# FindMeSAT_MB_1V3.net
KiCad netlist of a schematic drawn in EAGLE
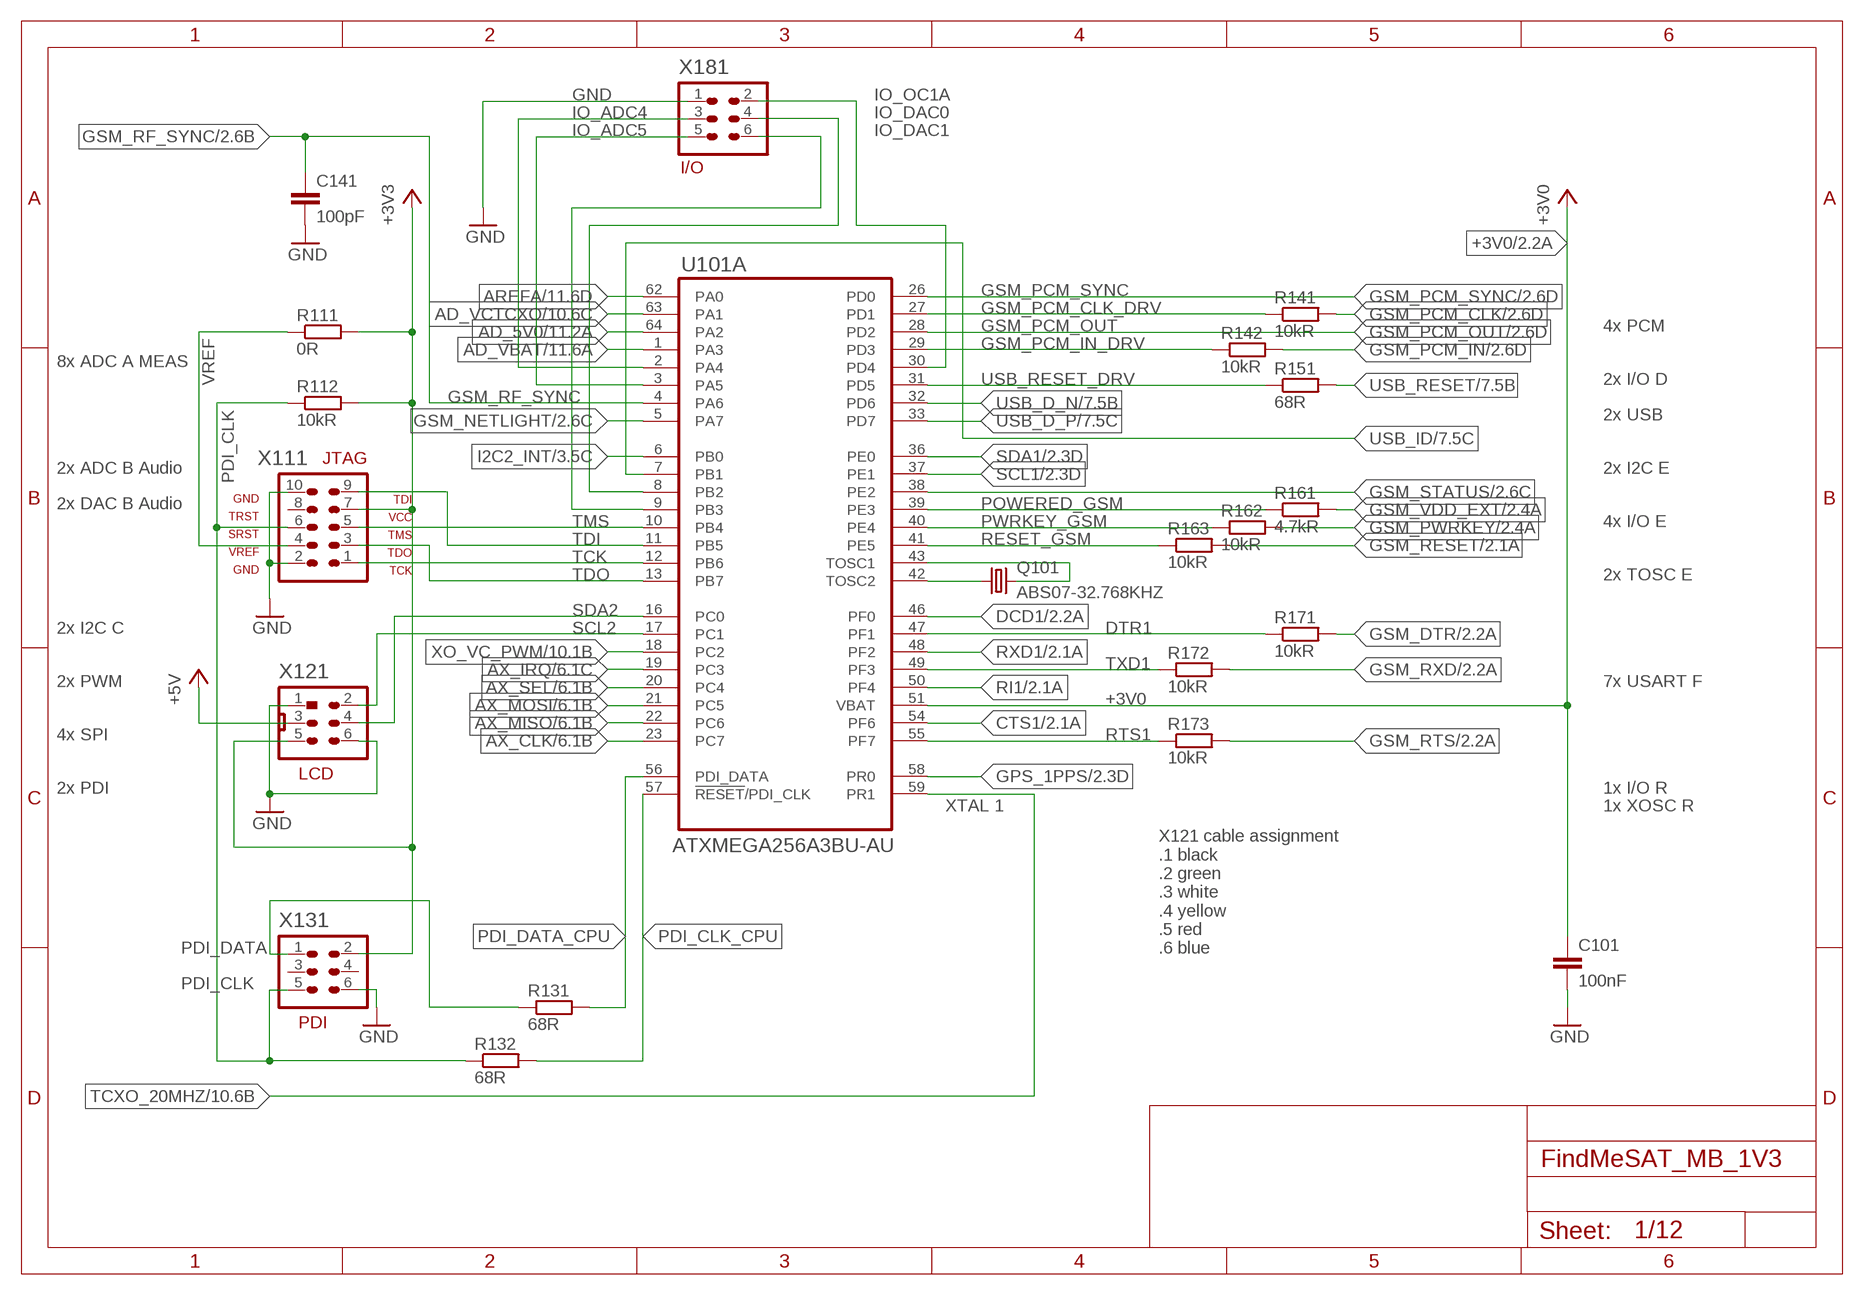
[diagram p0: schematic, sheet 1]
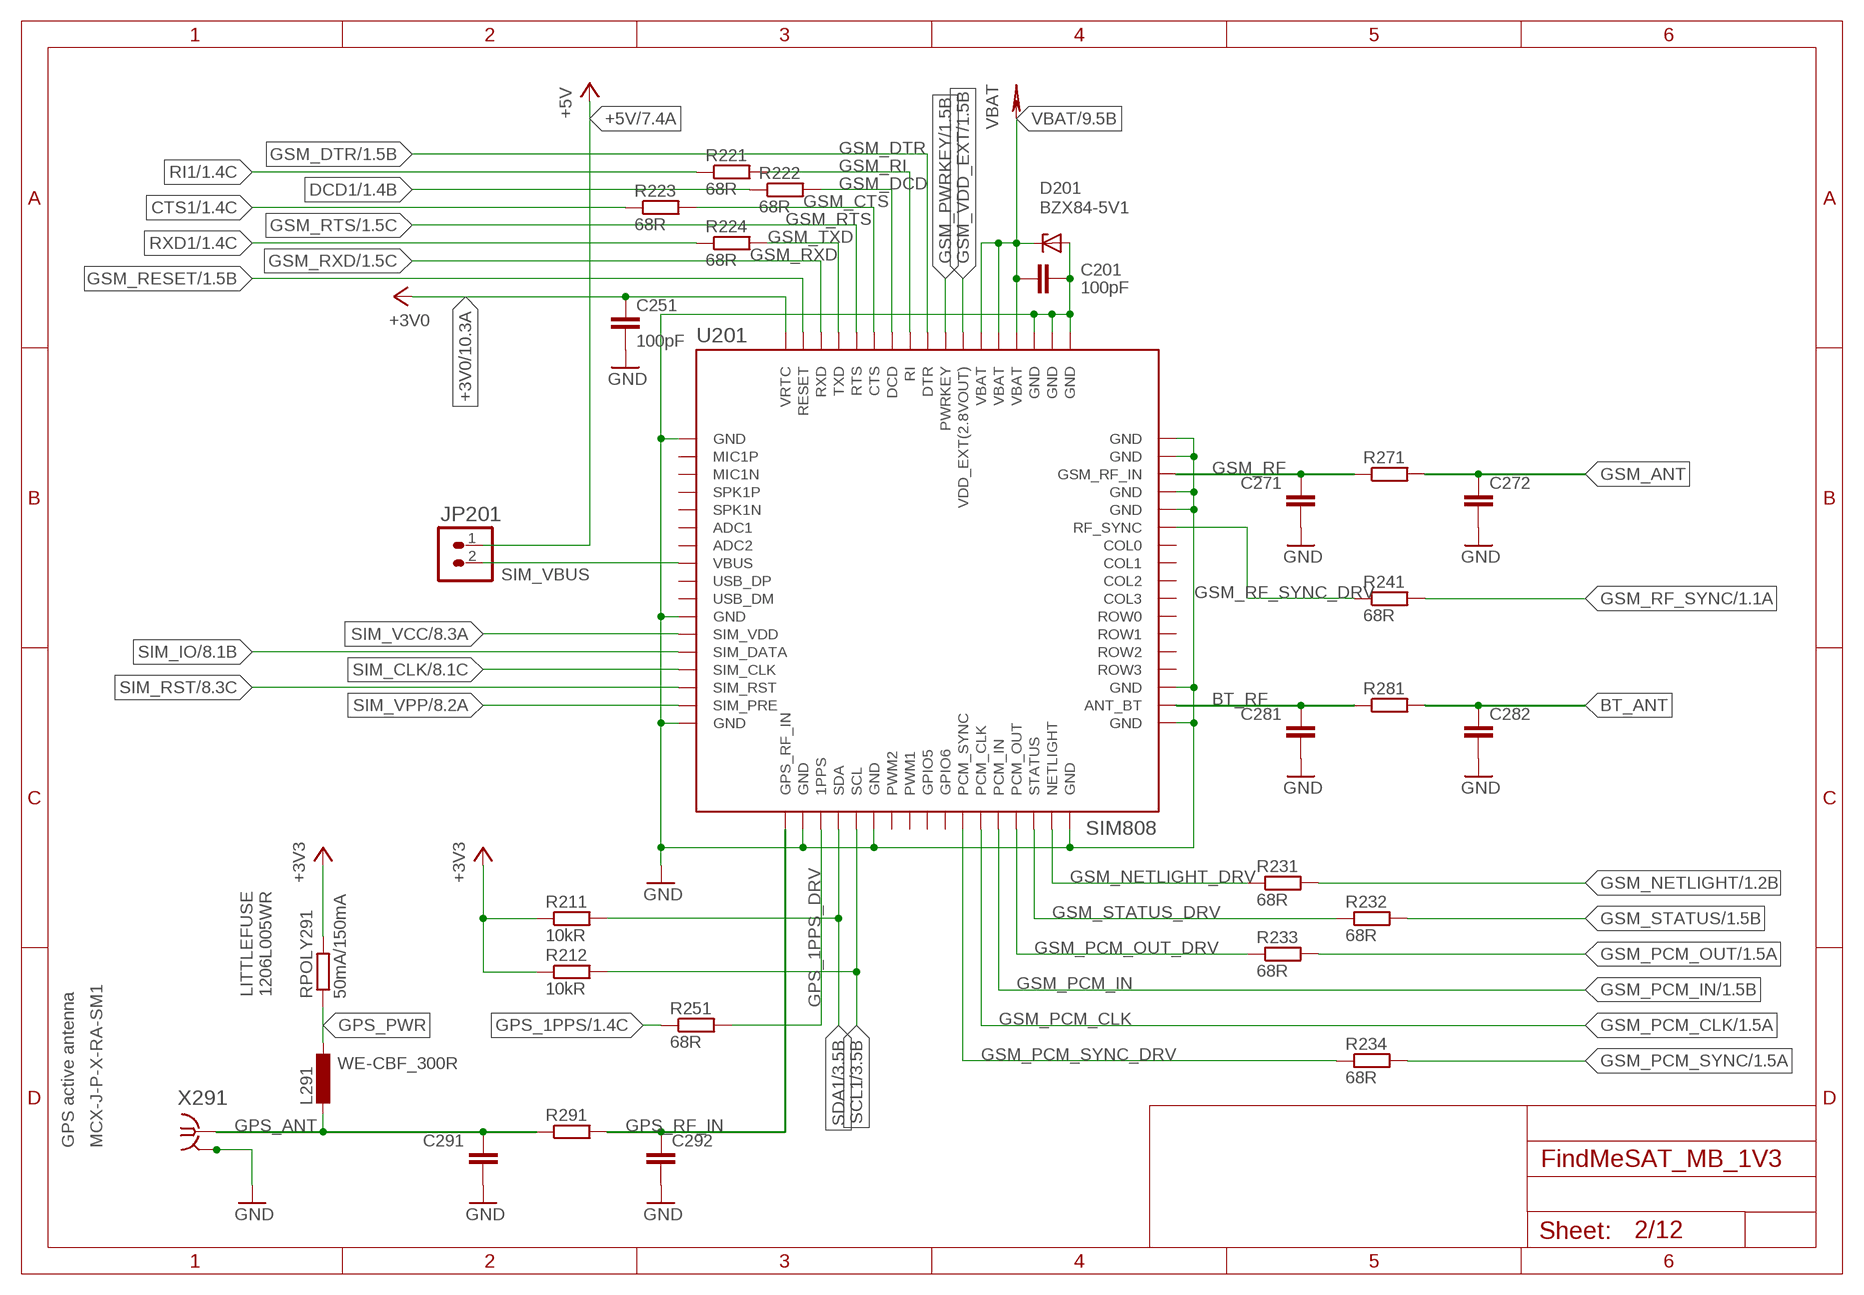
[diagram p1: schematic, sheet 2]
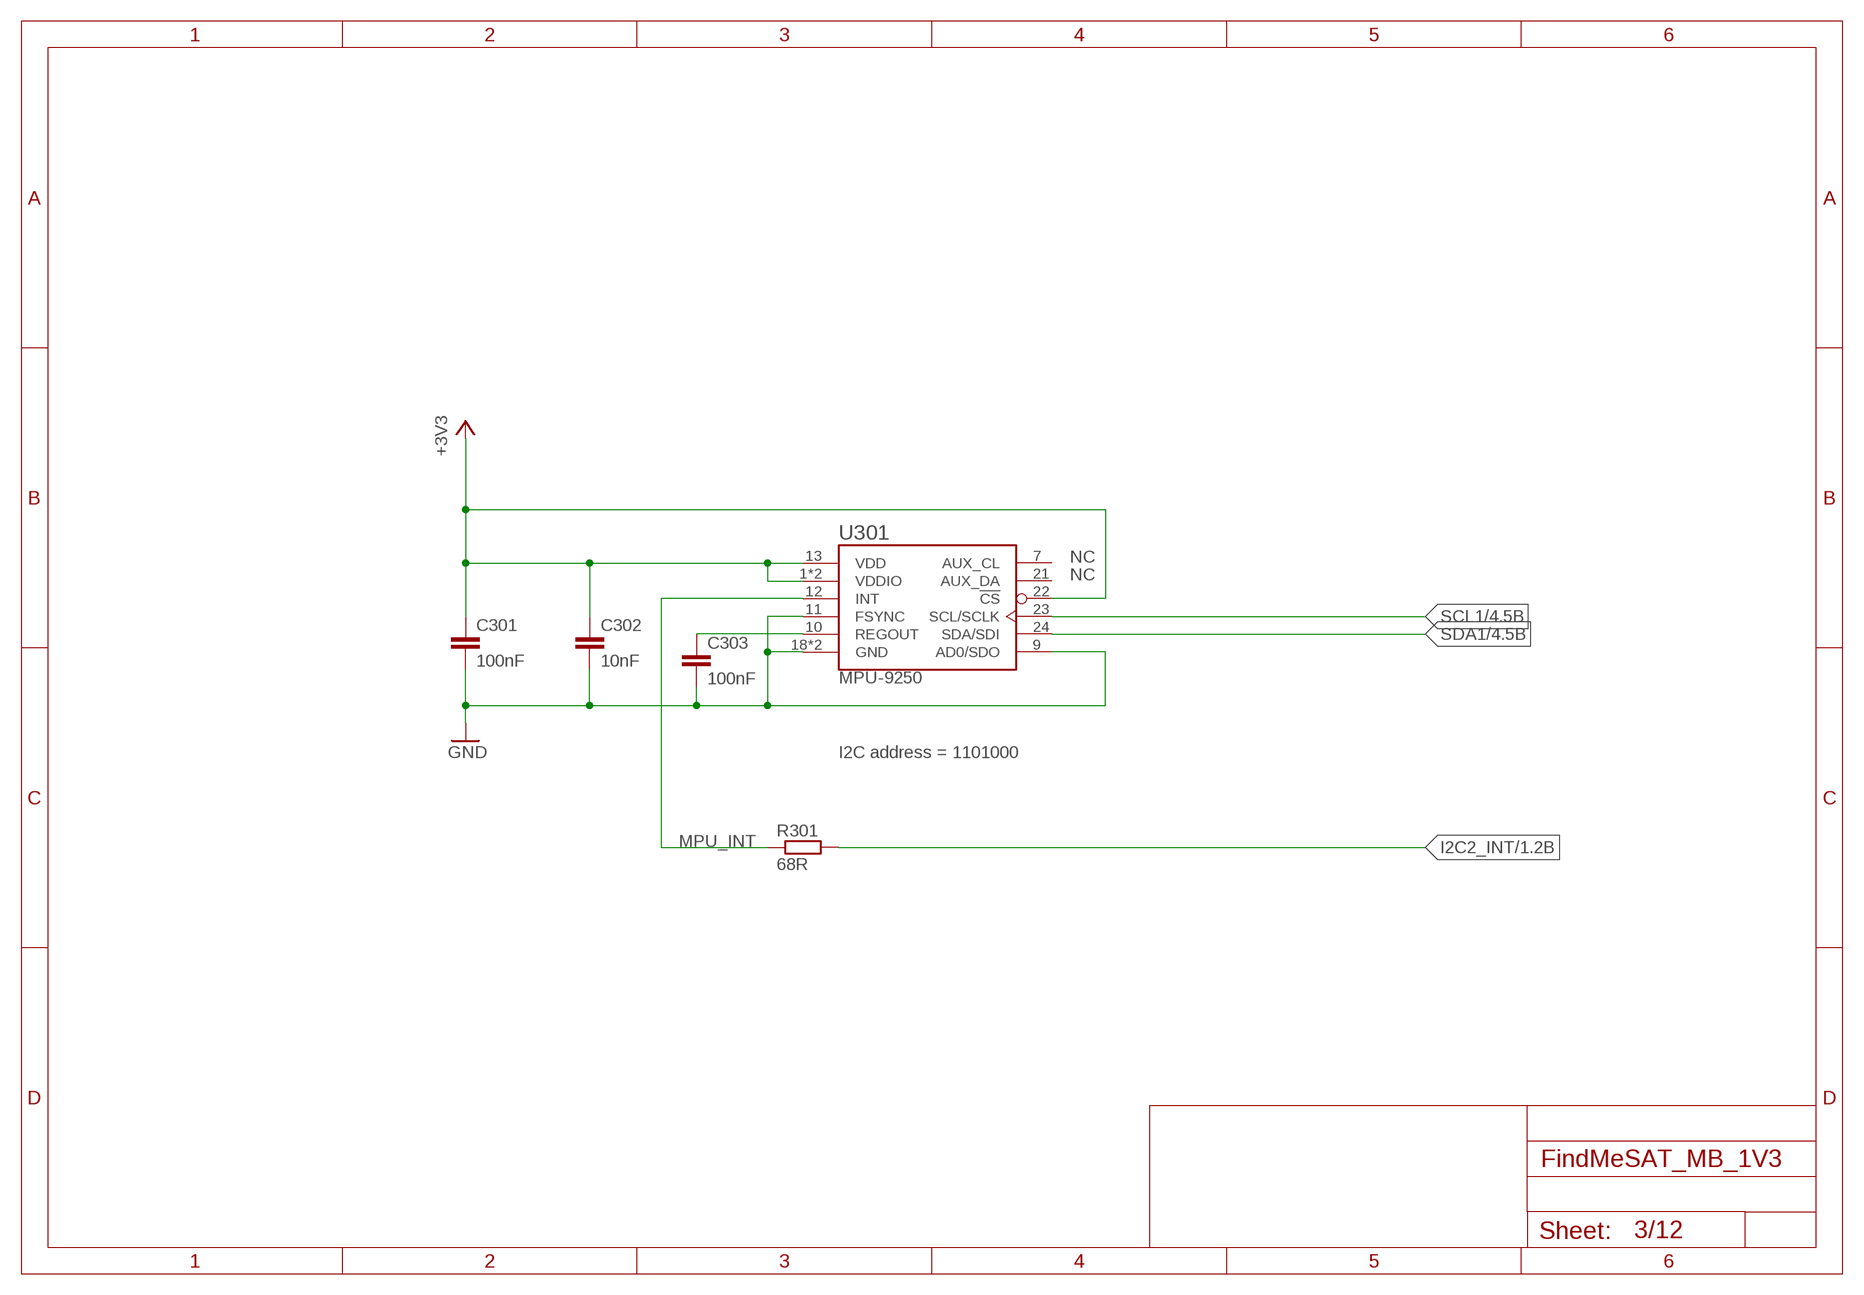
[diagram p2: schematic, sheet 3]
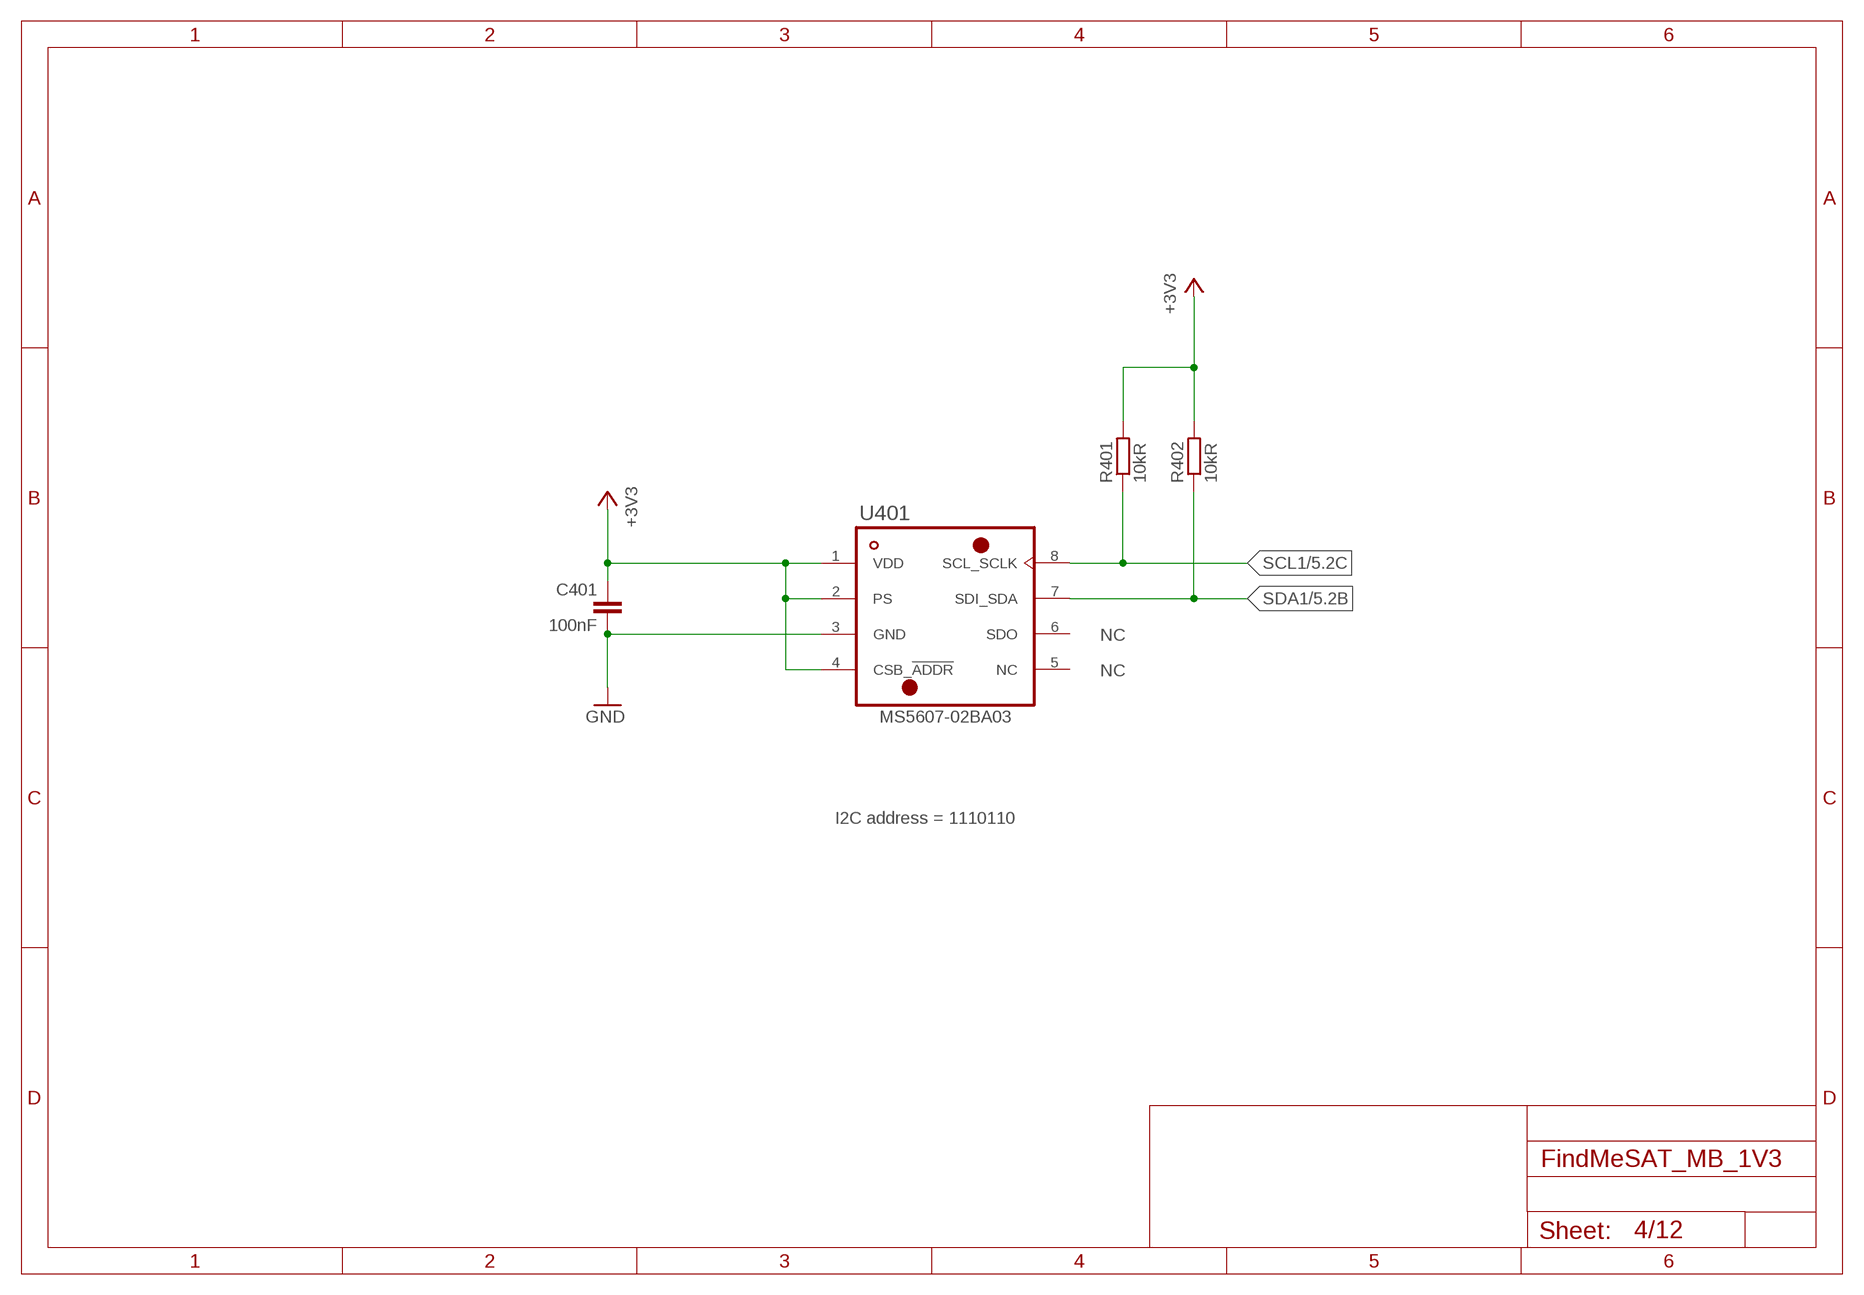
[diagram p3: schematic, sheet 4]
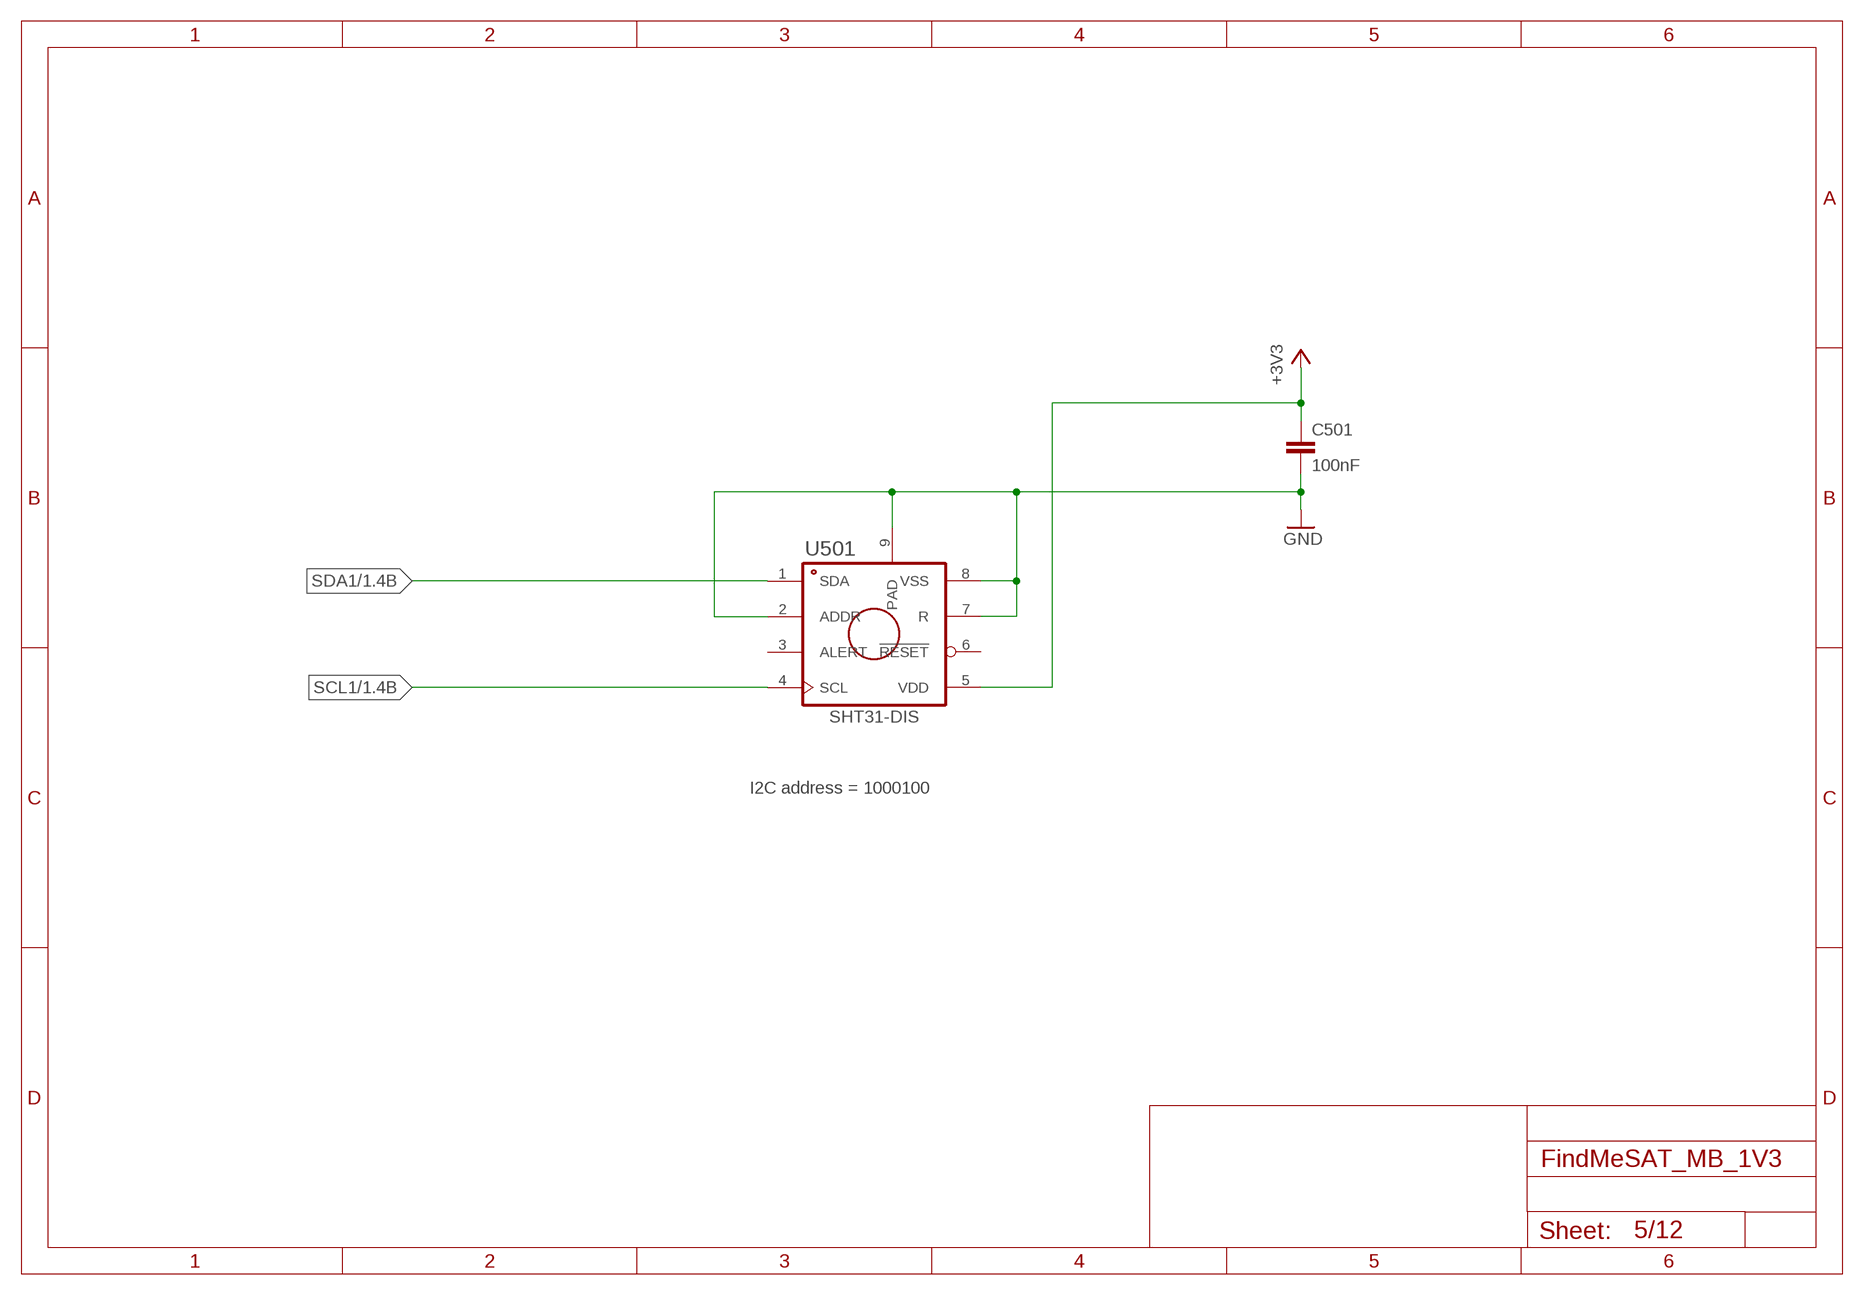
[diagram p4: schematic, sheet 5]
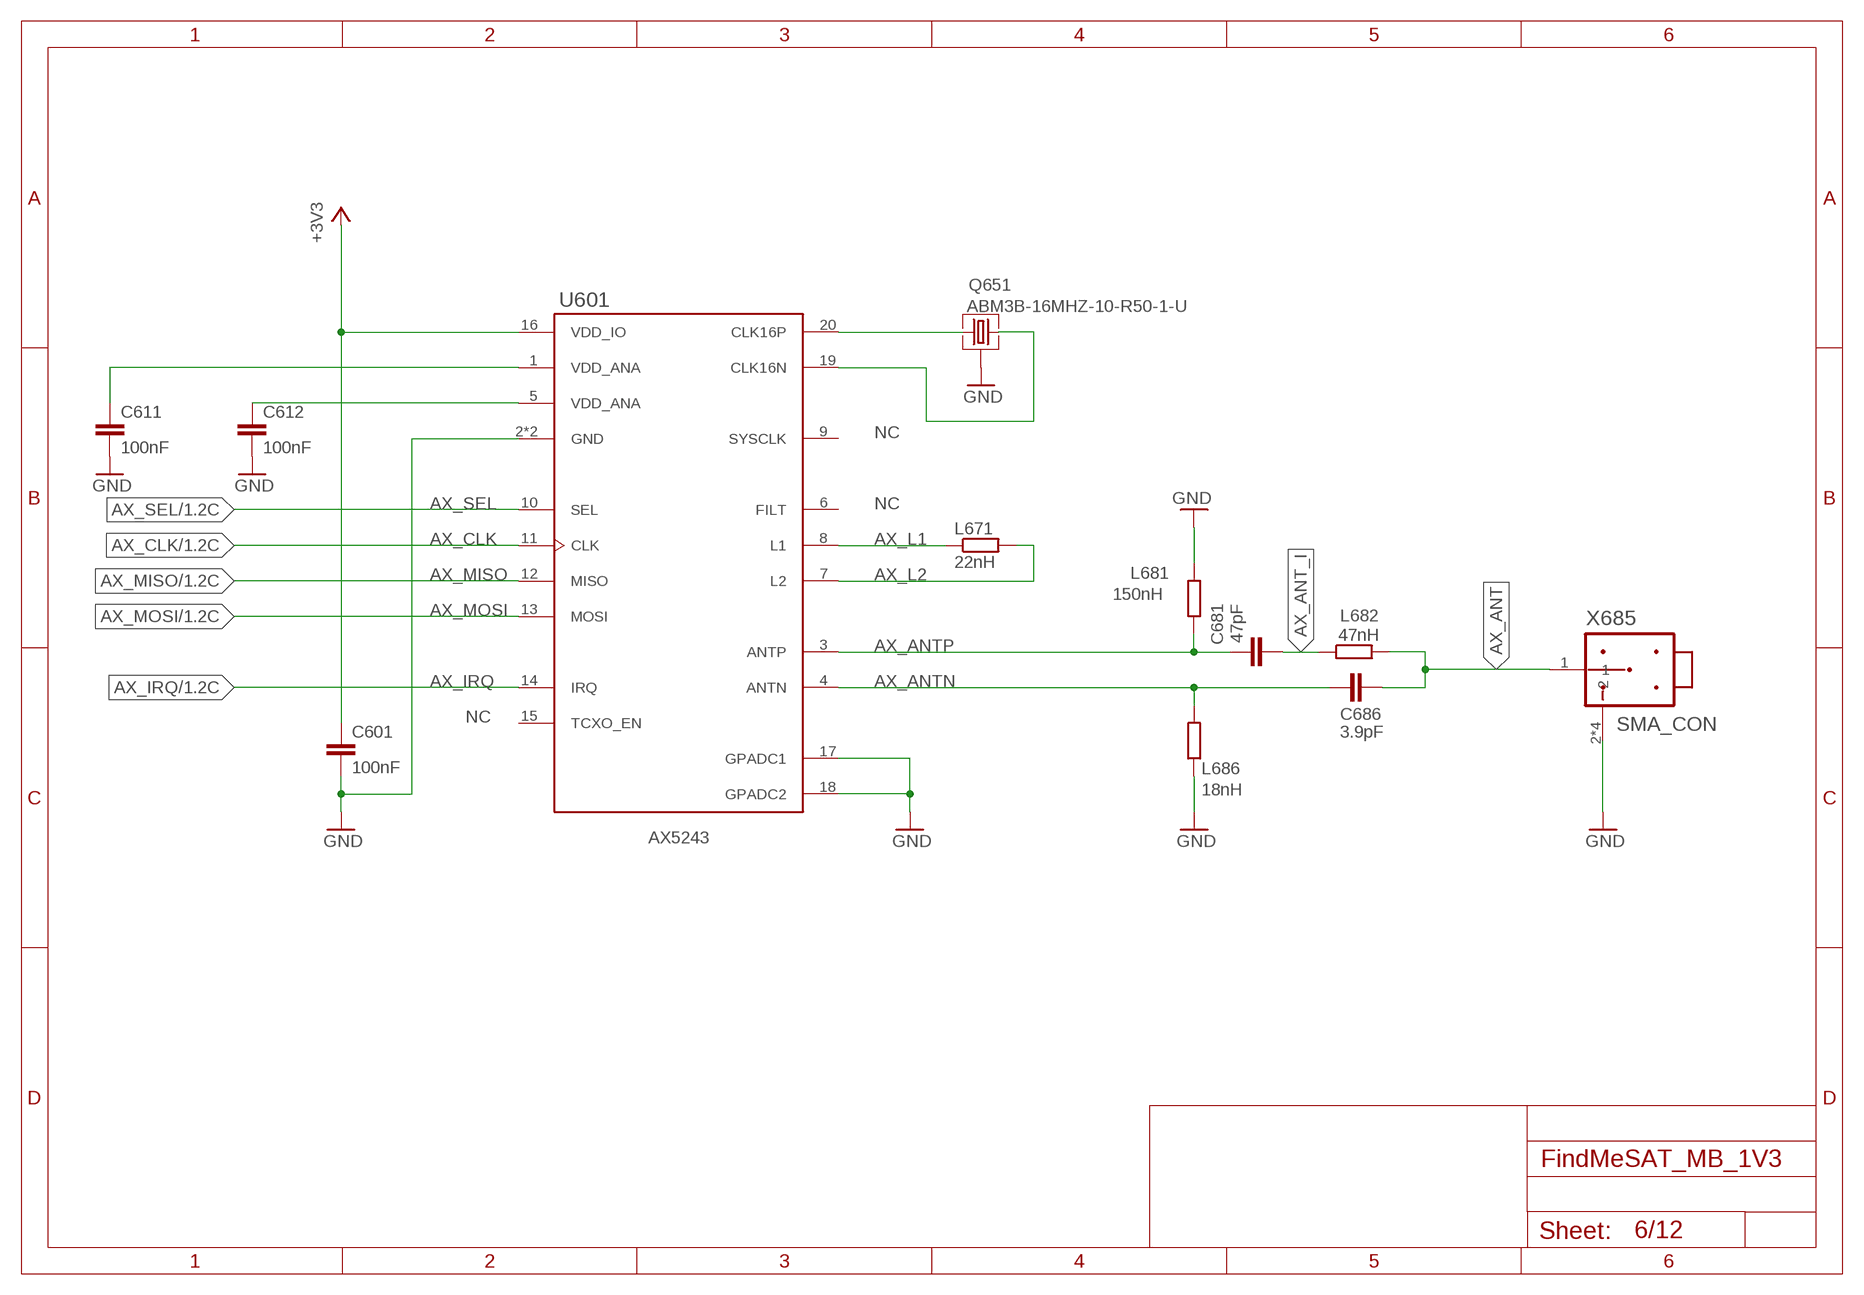
[diagram p5: schematic, sheet 6]
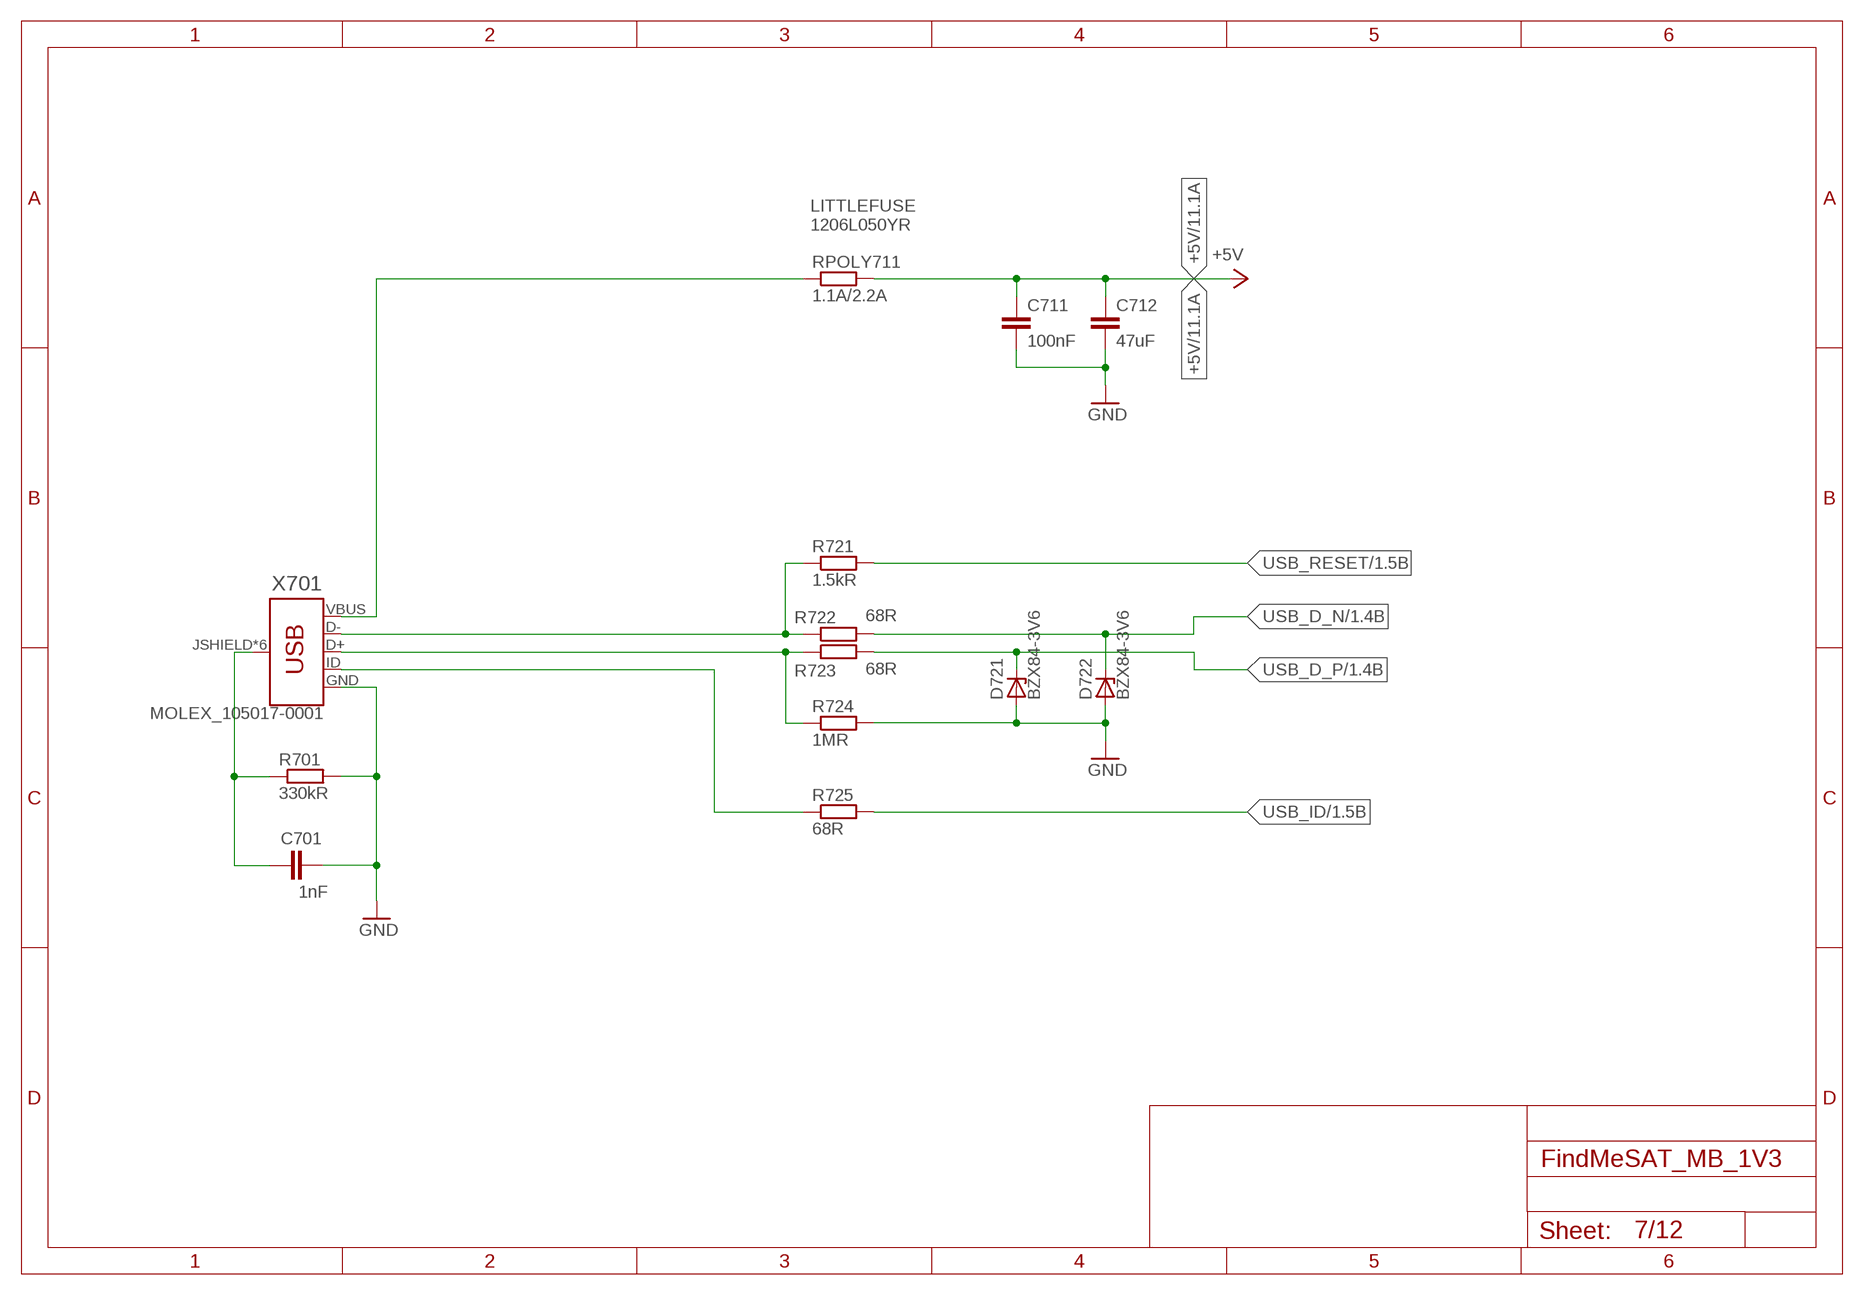
[diagram p6: schematic, sheet 7]
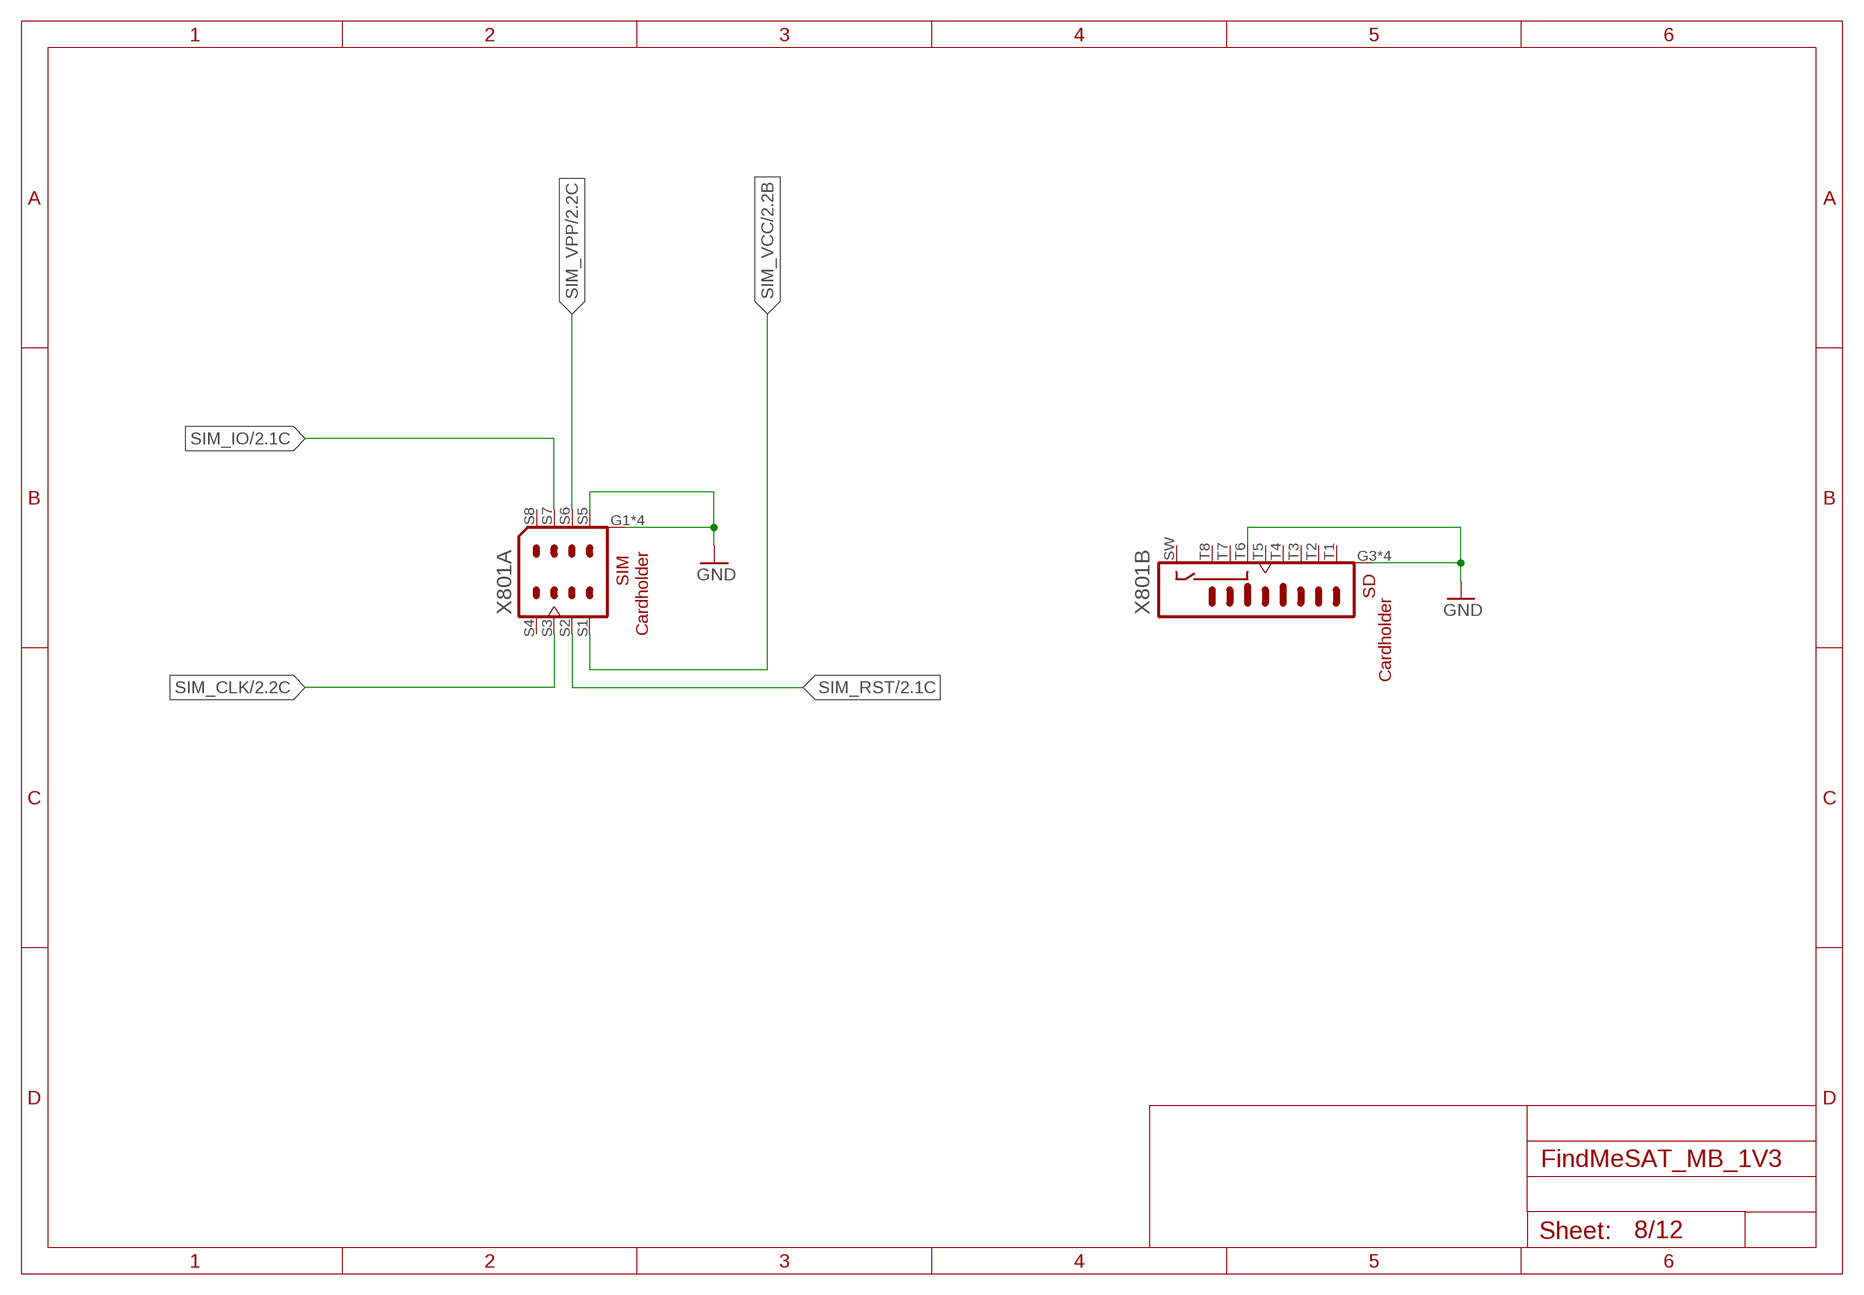
[diagram p7: schematic, sheet 8]
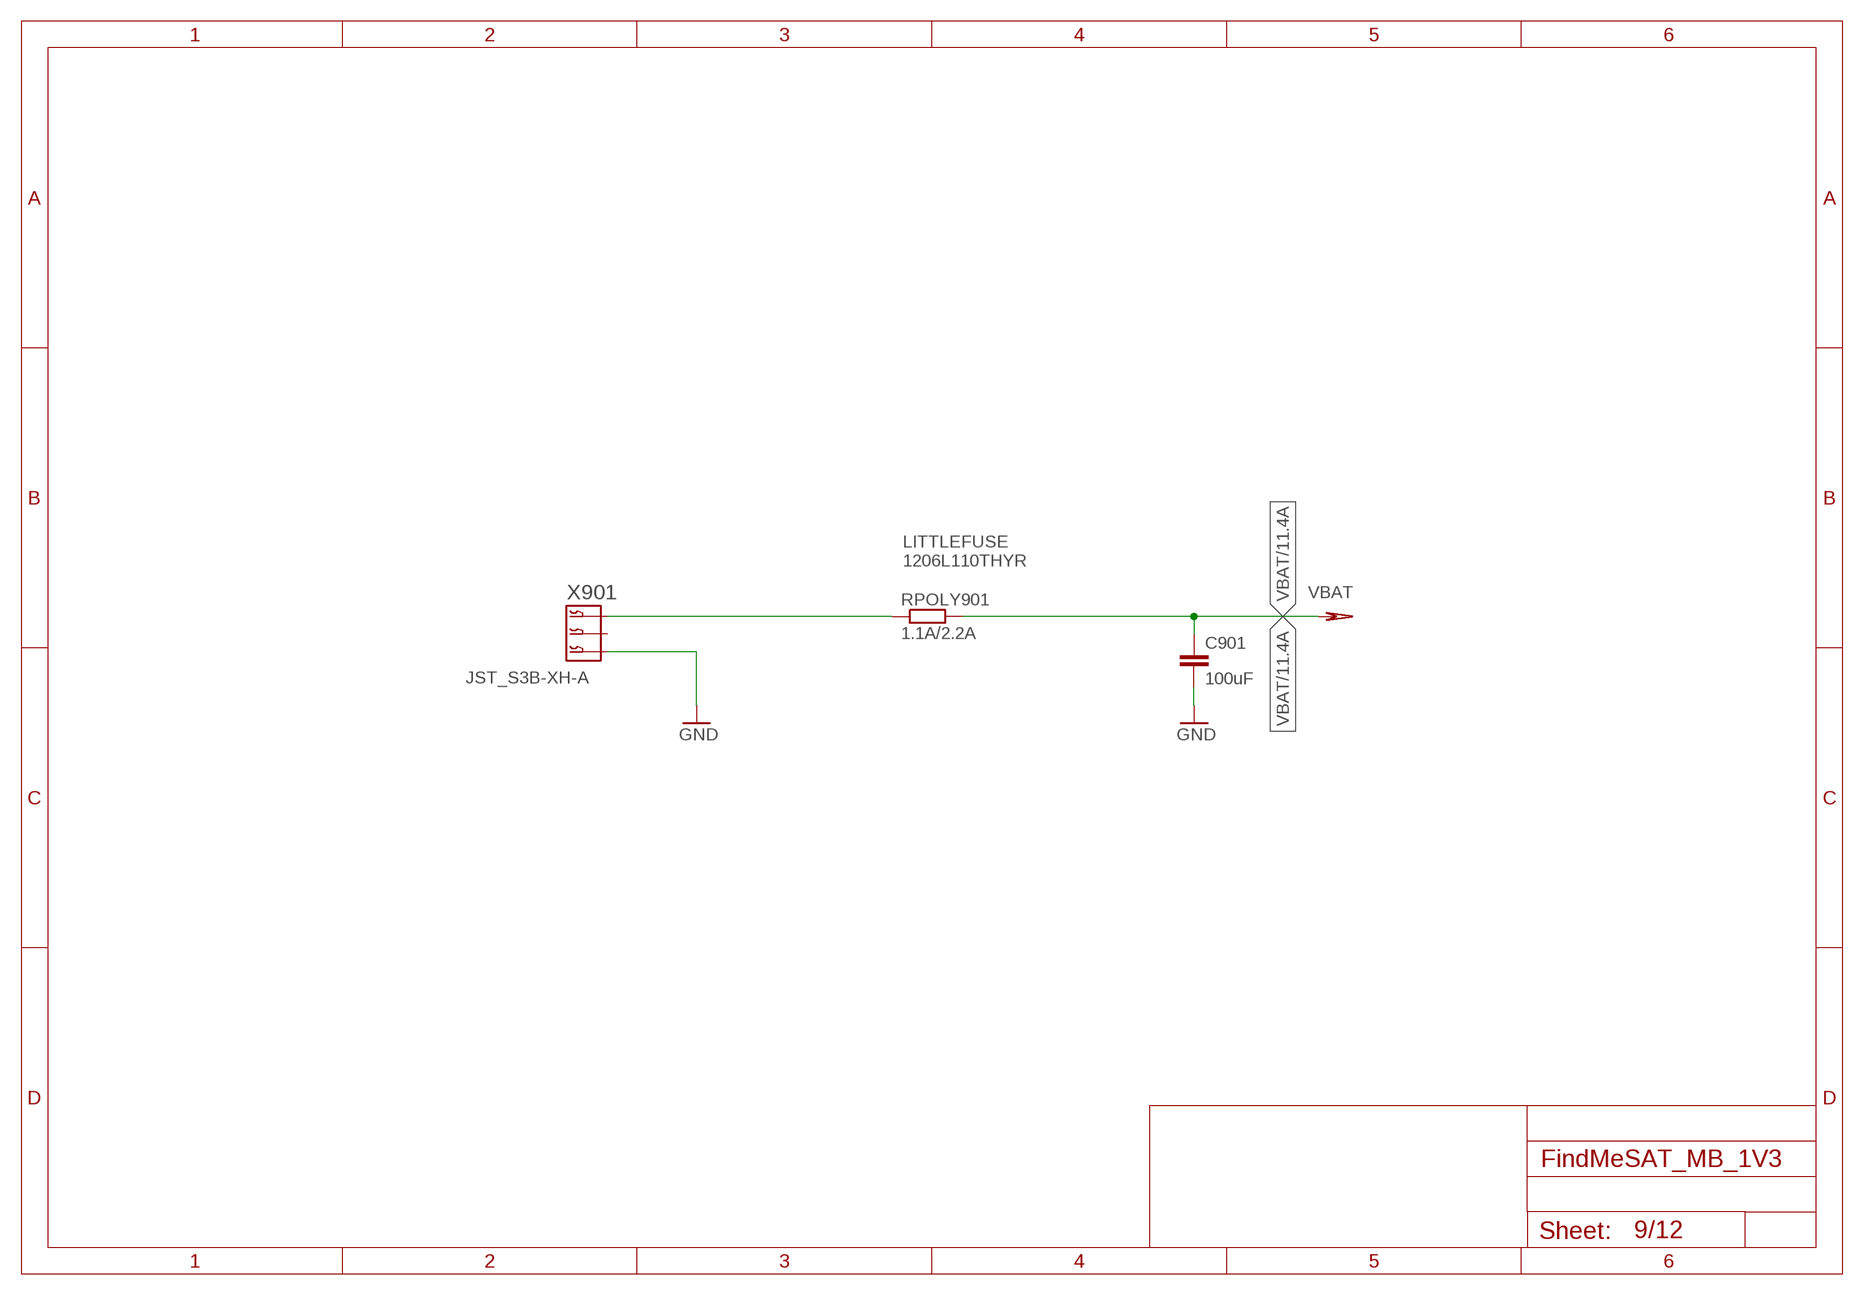
[diagram p8: schematic, sheet 9]
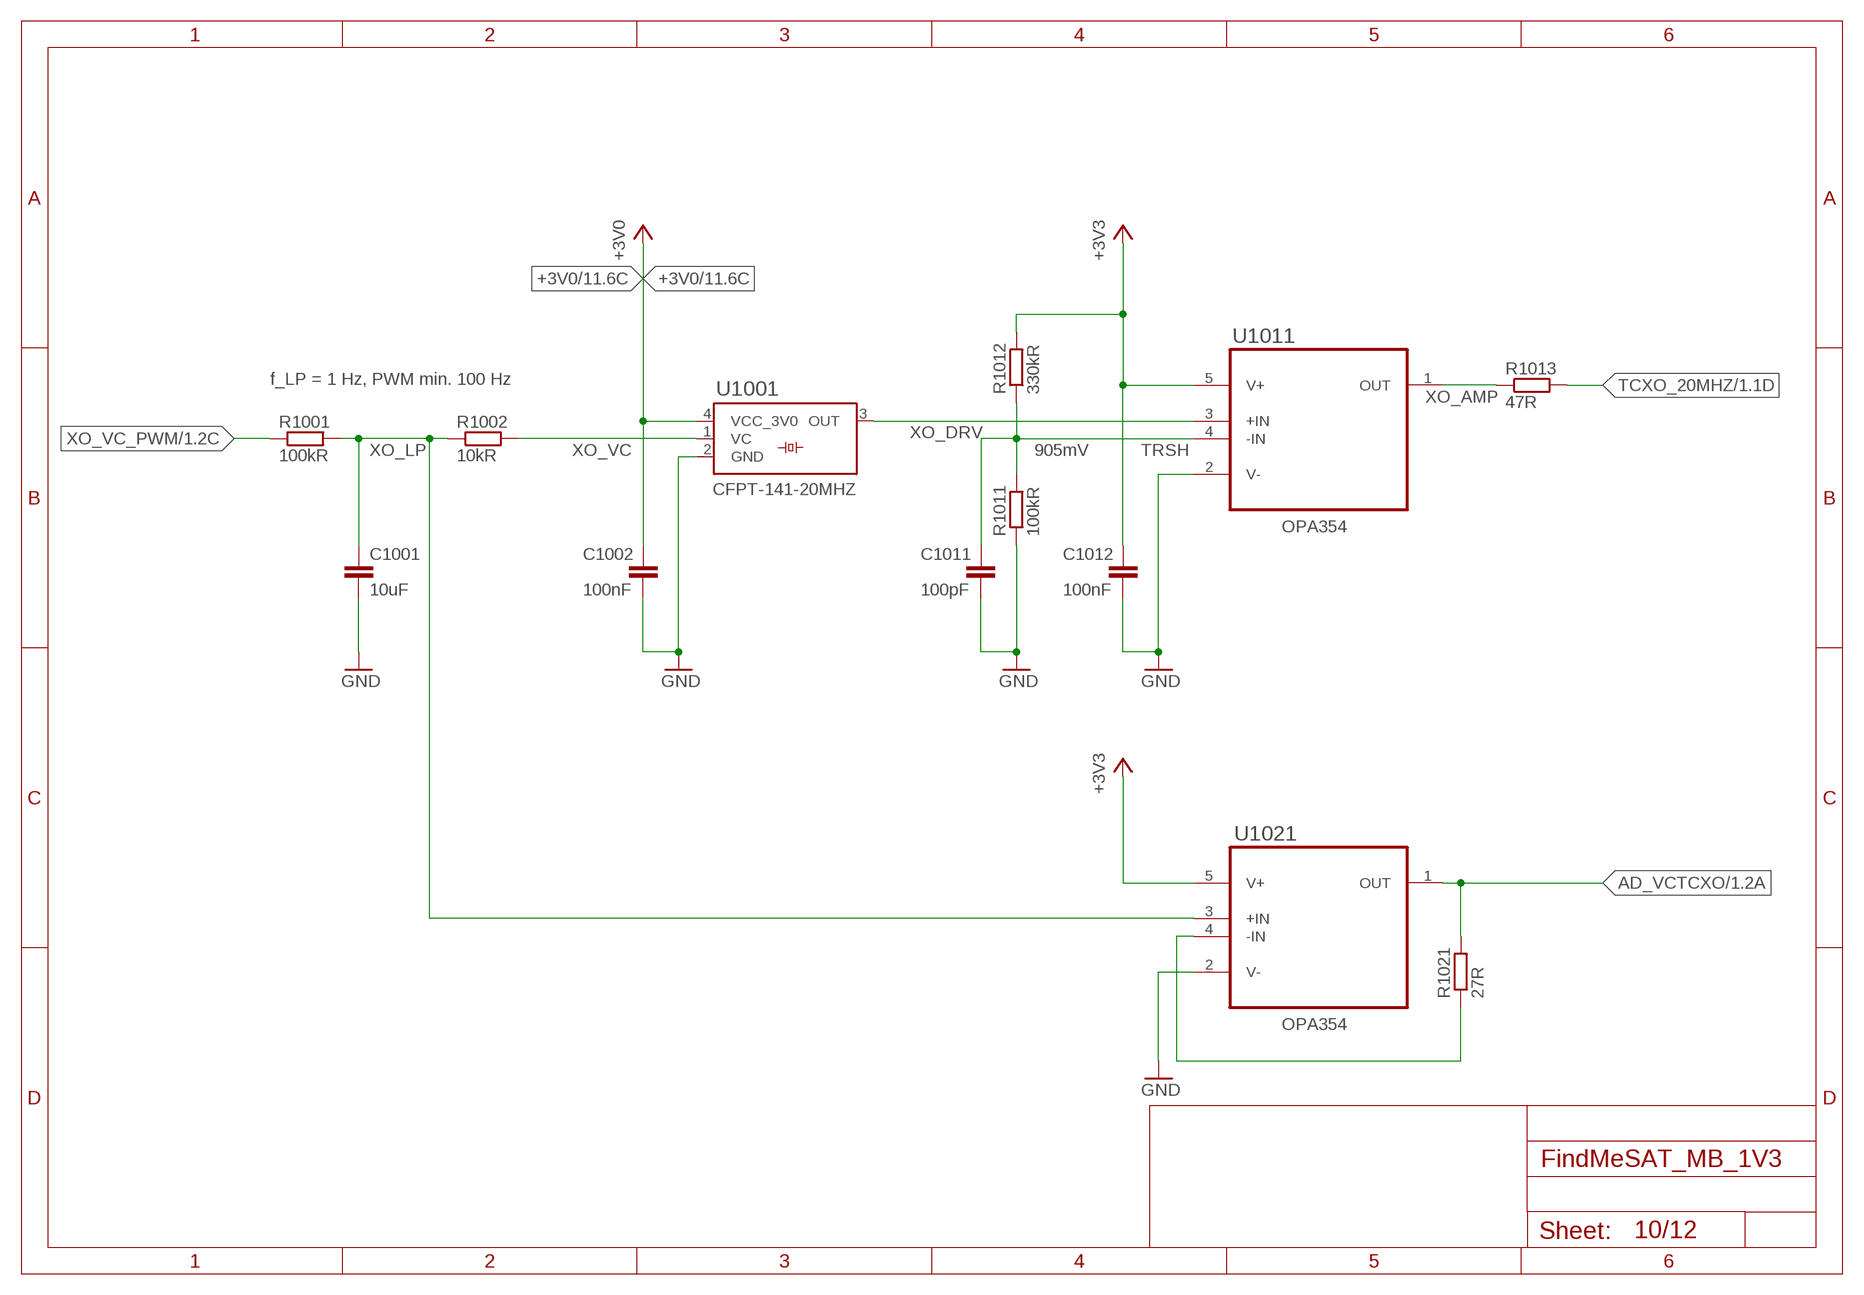
[diagram p9: schematic, sheet 10]
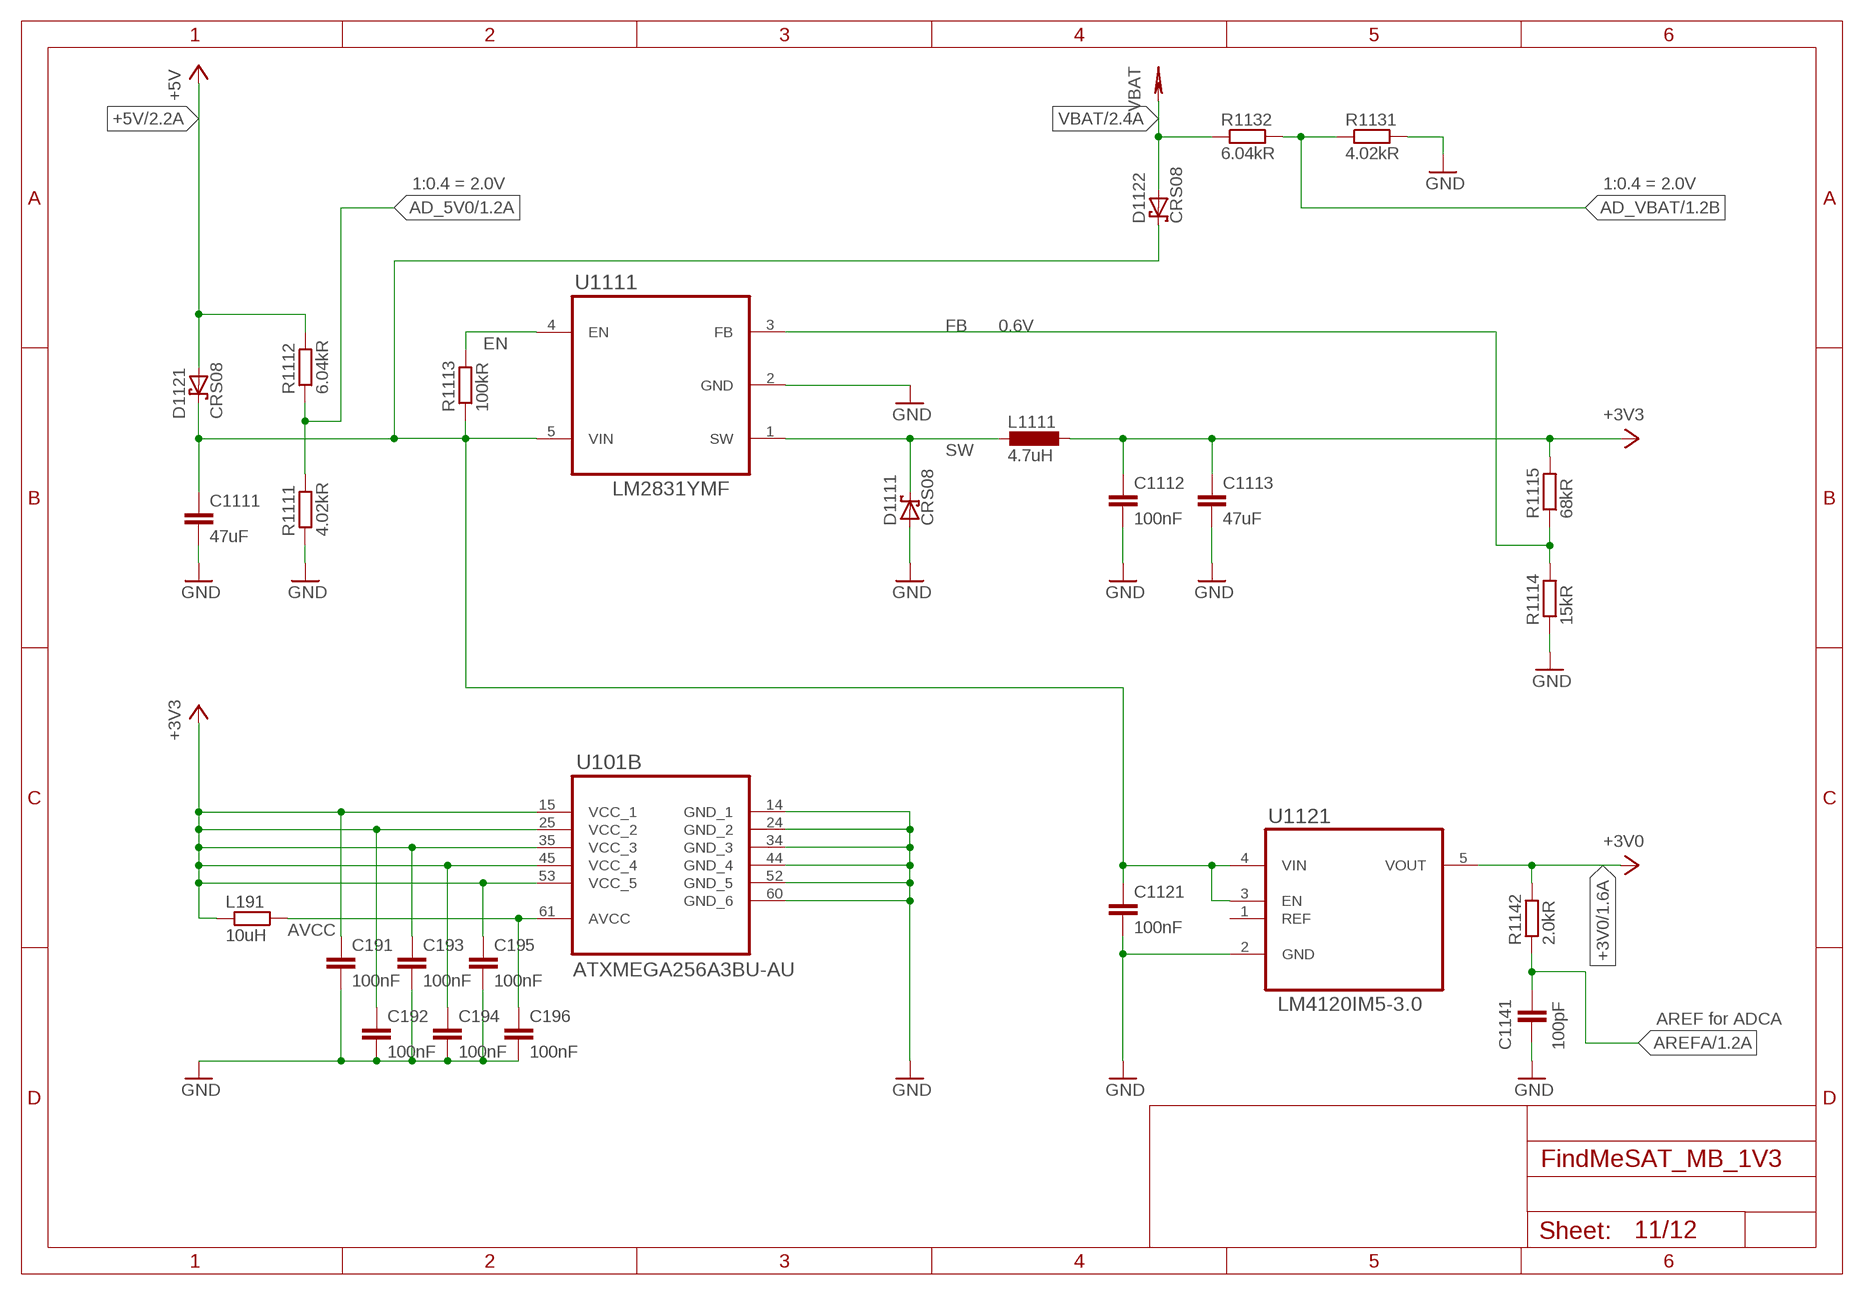
[diagram p10: schematic, sheet 11]
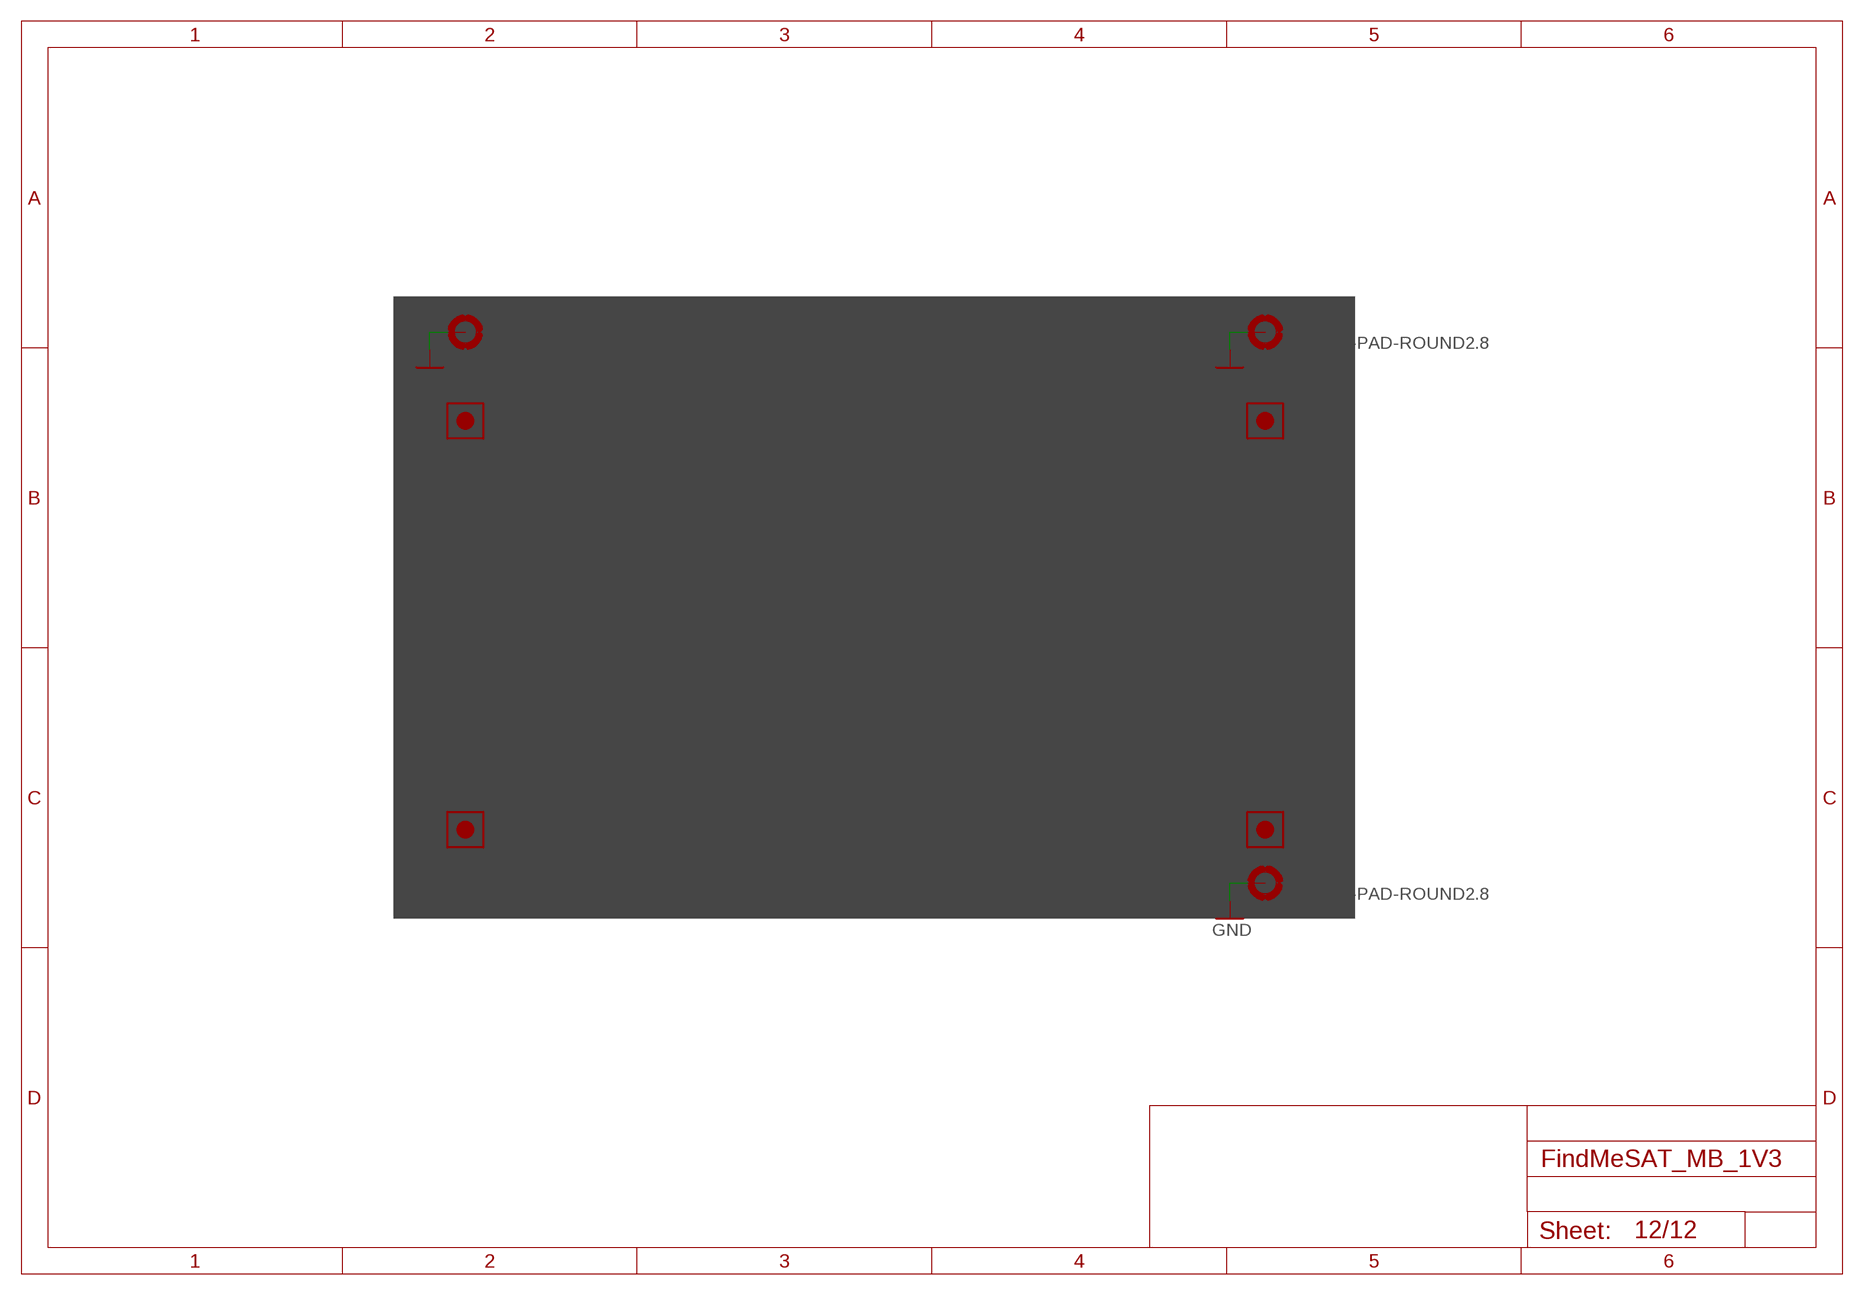
[diagram p11: schematic, sheet 12]

(export (version "E")
  (design (tool "Eeschema 10.0.6"))
  (components
    (comp (ref "FM1201")
      (value "FIDUCIAL_MARK_1MM")
      (footprint "eagle-import:FIDUCIAL_MARK_1MM")
      (libsource (lib "eagle-import") (part "FIDUCIAL_MARK_1MM"))
    )
    (comp (ref "FM1202")
      (value "FIDUCIAL_MARK_1MM")
      (footprint "eagle-import:FIDUCIAL_MARK_1MM")
      (libsource (lib "eagle-import") (part "FIDUCIAL_MARK_1MM"))
    )
    (comp (ref "FM1203")
      (value "FIDUCIAL_MARK_1MM")
      (footprint "eagle-import:FIDUCIAL_MARK_1MM")
      (libsource (lib "eagle-import") (part "FIDUCIAL_MARK_1MM"))
    )
    (comp (ref "FM1204")
      (value "FIDUCIAL_MARK_1MM")
      (footprint "eagle-import:FIDUCIAL_MARK_1MM")
      (libsource (lib "eagle-import") (part "FIDUCIAL_MARK_1MM"))
    )
    (comp (ref "H1201")
      (value "MOUNT-PAD-ROUND2.8")
      (footprint "eagle-import:2,8-PAD")
      (libsource (lib "eagle-import") (part "MOUNT-PAD-ROUND2.8"))
    )
    (comp (ref "H1203")
      (value "MOUNT-PAD-ROUND2.8")
      (footprint "eagle-import:2,8-PAD")
      (libsource (lib "eagle-import") (part "MOUNT-PAD-ROUND2.8"))
    )
    (comp (ref "H1204")
      (value "MOUNT-PAD-ROUND2.8")
      (footprint "eagle-import:2,8-PAD")
      (libsource (lib "eagle-import") (part "MOUNT-PAD-ROUND2.8"))
    )
    (comp (ref "C701")
      (value "1nF")
      (footprint "eagle-import:C0603")
      (libsource (lib "eagle-import") (part "C-EUC0603"))
    )
    (comp (ref "C711")
      (value "100nF")
      (footprint "eagle-import:C0603")
      (libsource (lib "eagle-import") (part "C-EUC0603"))
    )
    (comp (ref "C712")
      (value "47uF")
      (footprint "eagle-import:C0805")
      (libsource (lib "eagle-import") (part "C-EUC0805"))
    )
    (comp (ref "D721")
      (value "BZX84-3V6")
      (footprint "eagle-import:TO236")
      (libsource (lib "eagle-import") (part "BZX84CSMD"))
    )
    (comp (ref "D722")
      (value "BZX84-3V6")
      (footprint "eagle-import:TO236")
      (libsource (lib "eagle-import") (part "BZX84CSMD"))
    )
    (comp (ref "R701")
      (value "330kR")
      (footprint "eagle-import:R0603")
      (libsource (lib "eagle-import") (part "R-EU_R0603"))
    )
    (comp (ref "R721")
      (value "1.5kR")
      (footprint "eagle-import:R0603")
      (libsource (lib "eagle-import") (part "R-EU_R0603"))
    )
    (comp (ref "R722")
      (value "68R")
      (footprint "eagle-import:R0603")
      (libsource (lib "eagle-import") (part "R-EU_R0603"))
    )
    (comp (ref "R723")
      (value "68R")
      (footprint "eagle-import:R0603")
      (libsource (lib "eagle-import") (part "R-EU_R0603"))
    )
    (comp (ref "R724")
      (value "1MR")
      (footprint "eagle-import:R0603")
      (libsource (lib "eagle-import") (part "R-EU_R0603"))
    )
    (comp (ref "R725")
      (value "68R")
      (footprint "eagle-import:R0603")
      (libsource (lib "eagle-import") (part "R-EU_R0603"))
    )
    (comp (ref "RPOLY711")
      (value "1.1A/2.2A")
      (footprint "eagle-import:M1206")
      (libsource (lib "eagle-import") (part "R-EU_M1206"))
    )
    (comp (ref "X701")
      (value "MOLEX_105017-0001")
      (footprint "eagle-import:USB-B-MICRO-SMD_MOLEX-105017-0001")
      (libsource (lib "eagle-import") (part "USB_MICRO-B_MOLEX"))
    )
    (comp (ref "C501")
      (value "100nF")
      (footprint "eagle-import:C0603")
      (libsource (lib "eagle-import") (part "C-EUC0603"))
    )
    (comp (ref "U501")
      (value "SHT31-DIS")
      (footprint "eagle-import:DFN8_SHT")
      (libsource (lib "eagle-import") (part "SHT31-DIS"))
    )
    (comp (ref "C101")
      (value "100nF")
      (footprint "eagle-import:C0603")
      (libsource (lib "eagle-import") (part "C-EUC0603"))
    )
    (comp (ref "C141")
      (value "100pF")
      (footprint "eagle-import:C0603")
      (libsource (lib "eagle-import") (part "C-EUC0603"))
    )
    (comp (ref "Q101")
      (value "ABS07-32.768KHZ")
      (footprint "eagle-import:ABS07")
      (fields (field (name "MANUFACTURER") "ABS07-32.768KHZ-1-T"))
      (libsource (lib "eagle-import") (part "ABS07-32.768KHZ"))
    )
    (comp (ref "R111")
      (value "0R")
      (footprint "eagle-import:R0805")
      (libsource (lib "eagle-import") (part "R-EU_R0805"))
    )
    (comp (ref "R112")
      (value "10kR")
      (footprint "eagle-import:R0603")
      (libsource (lib "eagle-import") (part "R-EU_R0603"))
    )
    (comp (ref "R131")
      (value "68R")
      (footprint "eagle-import:R0603")
      (libsource (lib "eagle-import") (part "R-EU_R0603"))
    )
    (comp (ref "R132")
      (value "68R")
      (footprint "eagle-import:R0603")
      (libsource (lib "eagle-import") (part "R-EU_R0603"))
    )
    (comp (ref "R141")
      (value "10kR")
      (footprint "eagle-import:R0603")
      (libsource (lib "eagle-import") (part "R-EU_R0603"))
    )
    (comp (ref "R142")
      (value "10kR")
      (footprint "eagle-import:R0603")
      (libsource (lib "eagle-import") (part "R-EU_R0603"))
    )
    (comp (ref "R151")
      (value "68R")
      (footprint "eagle-import:R0603")
      (libsource (lib "eagle-import") (part "R-EU_R0603"))
    )
    (comp (ref "R161")
      (value "4.7kR")
      (footprint "eagle-import:R0603")
      (libsource (lib "eagle-import") (part "R-EU_R0603"))
    )
    (comp (ref "R162")
      (value "10kR")
      (footprint "eagle-import:R0603")
      (libsource (lib "eagle-import") (part "R-EU_R0603"))
    )
    (comp (ref "R163")
      (value "10kR")
      (footprint "eagle-import:R0603")
      (libsource (lib "eagle-import") (part "R-EU_R0603"))
    )
    (comp (ref "R171")
      (value "10kR")
      (footprint "eagle-import:R0603")
      (libsource (lib "eagle-import") (part "R-EU_R0603"))
    )
    (comp (ref "R172")
      (value "10kR")
      (footprint "eagle-import:R0603")
      (libsource (lib "eagle-import") (part "R-EU_R0603"))
    )
    (comp (ref "R173")
      (value "10kR")
      (footprint "eagle-import:R0603")
      (libsource (lib "eagle-import") (part "R-EU_R0603"))
    )
    (comp (ref "U101")
      (value "ATXMEGA256A3BU-AU")
      (footprint "eagle-import:QFP80P1600X1600X120-64N")
      (libsource (lib "eagle-import") (part "ATXMEGA256A3BU-AU"))
    )
    (comp (ref "X111")
      (value "AVR-JTAG-10")
      (footprint "eagle-import:AVR-JTAG-10")
      (libsource (lib "eagle-import") (part "AVR-JTAG-10"))
    )
    (comp (ref "X121")
      (value "MOLEX_90130_2X03")
      (footprint "eagle-import:MOLEX_90130_2X03")
      (libsource (lib "eagle-import") (part "MOLEX_90130_2X03"))
    )
    (comp (ref "X131")
      (value "HEADER-2X3")
      (footprint "eagle-import:2X03")
      (libsource (lib "eagle-import") (part "HEADER-2X3"))
    )
    (comp (ref "X181")
      (value "HEADER-2X3")
      (footprint "eagle-import:2X03")
      (libsource (lib "eagle-import") (part "HEADER-2X3"))
    )
    (comp (ref "C901")
      (value "100uF")
      (footprint "eagle-import:C0805")
      (libsource (lib "eagle-import") (part "C-EUC0805"))
    )
    (comp (ref "RPOLY901")
      (value "1.1A/2.2A")
      (footprint "eagle-import:M1206")
      (libsource (lib "eagle-import") (part "R-EU_M1206"))
    )
    (comp (ref "X901")
      (value "JST_S3B-XH-A")
      (footprint "eagle-import:JST_S3B-XH-A")
      (libsource (lib "eagle-import") (part "JST_S3B-XH-A"))
    )
    (comp (ref "C301")
      (value "100nF")
      (footprint "eagle-import:C0603")
      (libsource (lib "eagle-import") (part "C-EUC0603"))
    )
    (comp (ref "C302")
      (value "10nF")
      (footprint "eagle-import:C0603")
      (libsource (lib "eagle-import") (part "C-EUC0603"))
    )
    (comp (ref "C303")
      (value "100nF")
      (footprint "eagle-import:C0603")
      (libsource (lib "eagle-import") (part "C-EUC0603"))
    )
    (comp (ref "R301")
      (value "68R")
      (footprint "eagle-import:R0603")
      (libsource (lib "eagle-import") (part "R-EU_R0603"))
    )
    (comp (ref "U301")
      (value "MPU-9250")
      (footprint "eagle-import:QFN24-3X3")
      (libsource (lib "eagle-import") (part "MPU-9250"))
    )
    (comp (ref "C1001")
      (value "10uF")
      (footprint "eagle-import:C0805")
      (libsource (lib "eagle-import") (part "C-EUC0805"))
    )
    (comp (ref "C1002")
      (value "100nF")
      (footprint "eagle-import:C0603")
      (libsource (lib "eagle-import") (part "C-EUC0603"))
    )
    (comp (ref "C1011")
      (value "100pF")
      (footprint "eagle-import:C0603")
      (libsource (lib "eagle-import") (part "C-EUC0603"))
    )
    (comp (ref "C1012")
      (value "100nF")
      (footprint "eagle-import:C0603")
      (libsource (lib "eagle-import") (part "C-EUC0603"))
    )
    (comp (ref "R1001")
      (value "100kR")
      (footprint "eagle-import:R0603")
      (libsource (lib "eagle-import") (part "R-EU_R0603"))
    )
    (comp (ref "R1002")
      (value "10kR")
      (footprint "eagle-import:R0603")
      (libsource (lib "eagle-import") (part "R-EU_R0603"))
    )
    (comp (ref "R1011")
      (value "100kR")
      (footprint "eagle-import:R0603")
      (libsource (lib "eagle-import") (part "R-EU_R0603"))
    )
    (comp (ref "R1012")
      (value "330kR")
      (footprint "eagle-import:R0603")
      (libsource (lib "eagle-import") (part "R-EU_R0603"))
    )
    (comp (ref "R1013")
      (value "47R")
      (footprint "eagle-import:R0603")
      (libsource (lib "eagle-import") (part "R-EU_R0603"))
    )
    (comp (ref "R1021")
      (value "27R")
      (footprint "eagle-import:R0603")
      (libsource (lib "eagle-import") (part "R-EU_R0603"))
    )
    (comp (ref "U1001")
      (value "CFPT-141-20MHZ")
      (footprint "eagle-import:CFPT-141")
      (fields (field (name "MF") "IQD-FREQUENCY-PRODUCTS") (field (name "MPN") "LFTVXO022175"))
      (libsource (lib "eagle-import") (part "CFPT-141-20MHZ"))
    )
    (comp (ref "U1011")
      (value "OPA354")
      (footprint "eagle-import:SOT-23-5")
      (fields (field (name "MPN") "OPA354AIDBVT"))
      (libsource (lib "eagle-import") (part "OPA354"))
    )
    (comp (ref "U1021")
      (value "OPA354")
      (footprint "eagle-import:SOT-23-5")
      (fields (field (name "MPN") "OPA354AIDBVT"))
      (libsource (lib "eagle-import") (part "OPA354"))
    )
    (comp (ref "X801")
      (value "MICROSIM-8P_SDCARD-8P_MOLEX-104642-1610")
      (footprint "eagle-import:MICROSIM-8P_SDCARD-8P_MOLEX-104642-1610")
      (fields (field (name "MPN") "MOLEX-104642-1610"))
      (libsource (lib "eagle-import") (part "MICROSIM-8P_SDCARD-8P_MOLEX-104642-1610"))
    )
    (comp (ref "C601")
      (value "100nF")
      (footprint "eagle-import:C0603")
      (libsource (lib "eagle-import") (part "C-EUC0603"))
    )
    (comp (ref "C611")
      (value "100nF")
      (footprint "eagle-import:C0603")
      (libsource (lib "eagle-import") (part "C-EUC0603"))
    )
    (comp (ref "C612")
      (value "100nF")
      (footprint "eagle-import:C0603")
      (libsource (lib "eagle-import") (part "C-EUC0603"))
    )
    (comp (ref "C681")
      (value "47pF")
      (footprint "eagle-import:C0603")
      (libsource (lib "eagle-import") (part "C-EUC0603"))
    )
    (comp (ref "C686")
      (value "3.9pF")
      (footprint "eagle-import:C0603")
      (libsource (lib "eagle-import") (part "C-EUC0603"))
    )
    (comp (ref "L671")
      (value "22nH")
      (footprint "eagle-import:R0603")
      (libsource (lib "eagle-import") (part "R-EU_R0603"))
    )
    (comp (ref "L681")
      (value "150nH")
      (footprint "eagle-import:R0603")
      (libsource (lib "eagle-import") (part "R-EU_R0603"))
    )
    (comp (ref "L682")
      (value "47nH")
      (footprint "eagle-import:R0603")
      (libsource (lib "eagle-import") (part "R-EU_R0603"))
    )
    (comp (ref "L686")
      (value "18nH")
      (footprint "eagle-import:R0603")
      (libsource (lib "eagle-import") (part "R-EU_R0603"))
    )
    (comp (ref "Q651")
      (value "ABM3B-16MHZ-10-R50-1-U")
      (footprint "eagle-import:ABM03B")
      (libsource (lib "eagle-import") (part "ABM03B-16.000MHZ"))
    )
    (comp (ref "U601")
      (value "AX5243")
      (footprint "eagle-import:QFN20-4X4-0P5-PAD")
      (libsource (lib "eagle-import") (part "AX5243"))
    )
    (comp (ref "X685")
      (value "SMA_CON")
      (footprint "eagle-import:SMA_SMT_AMPHENOL_901-143")
      (fields (field (name "MPN") "901-143"))
      (libsource (lib "eagle-import") (part "SMA_SMT_AMPHENOL-901-143"))
    )
    (comp (ref "C401")
      (value "100nF")
      (footprint "eagle-import:C0603")
      (libsource (lib "eagle-import") (part "C-EUC0603"))
    )
    (comp (ref "R401")
      (value "10kR")
      (footprint "eagle-import:R0603")
      (libsource (lib "eagle-import") (part "R-EU_R0603"))
    )
    (comp (ref "R402")
      (value "10kR")
      (footprint "eagle-import:R0603")
      (libsource (lib "eagle-import") (part "R-EU_R0603"))
    )
    (comp (ref "U401")
      (value "MS5607-02BA03")
      (footprint "eagle-import:MS5607-02BA")
      (libsource (lib "eagle-import") (part "MS5607-02BA03"))
    )
    (comp (ref "C201")
      (value "100pF")
      (footprint "eagle-import:C0603")
      (libsource (lib "eagle-import") (part "C-EUC0603"))
    )
    (comp (ref "C251")
      (value "100pF")
      (footprint "eagle-import:C0603")
      (libsource (lib "eagle-import") (part "C-EUC0603"))
    )
    (comp (ref "C271")
      (value "C-EUC0603")
      (footprint "eagle-import:C0603")
      (libsource (lib "eagle-import") (part "C-EUC0603"))
    )
    (comp (ref "C272")
      (value "C-EUC0603")
      (footprint "eagle-import:C0603")
      (libsource (lib "eagle-import") (part "C-EUC0603"))
    )
    (comp (ref "C281")
      (value "C-EUC0603")
      (footprint "eagle-import:C0603")
      (libsource (lib "eagle-import") (part "C-EUC0603"))
    )
    (comp (ref "C282")
      (value "C-EUC0603")
      (footprint "eagle-import:C0603")
      (libsource (lib "eagle-import") (part "C-EUC0603"))
    )
    (comp (ref "C291")
      (value "C-EUC0603")
      (footprint "eagle-import:C0603")
      (libsource (lib "eagle-import") (part "C-EUC0603"))
    )
    (comp (ref "C292")
      (value "C-EUC0603")
      (footprint "eagle-import:C0603")
      (libsource (lib "eagle-import") (part "C-EUC0603"))
    )
    (comp (ref "D201")
      (value "BZX84-5V1")
      (footprint "eagle-import:TO236")
      (libsource (lib "eagle-import") (part "BZX84CSMD"))
    )
    (comp (ref "JP201")
      (value "POW")
      (footprint "eagle-import:1X02")
      (libsource (lib "eagle-import") (part "HEADER-1X2"))
    )
    (comp (ref "L291")
      (value "WE-CBF_300R")
      (footprint "eagle-import:L3216C")
      (libsource (lib "eagle-import") (part "L-EUL3216C"))
    )
    (comp (ref "R211")
      (value "10kR")
      (footprint "eagle-import:R0603")
      (libsource (lib "eagle-import") (part "R-EU_R0603"))
    )
    (comp (ref "R212")
      (value "10kR")
      (footprint "eagle-import:R0603")
      (libsource (lib "eagle-import") (part "R-EU_R0603"))
    )
    (comp (ref "R221")
      (value "68R")
      (footprint "eagle-import:R0603")
      (libsource (lib "eagle-import") (part "R-EU_R0603"))
    )
    (comp (ref "R222")
      (value "68R")
      (footprint "eagle-import:R0603")
      (libsource (lib "eagle-import") (part "R-EU_R0603"))
    )
    (comp (ref "R223")
      (value "68R")
      (footprint "eagle-import:R0603")
      (libsource (lib "eagle-import") (part "R-EU_R0603"))
    )
    (comp (ref "R224")
      (value "68R")
      (footprint "eagle-import:R0603")
      (libsource (lib "eagle-import") (part "R-EU_R0603"))
    )
    (comp (ref "R231")
      (value "68R")
      (footprint "eagle-import:R0603")
      (libsource (lib "eagle-import") (part "R-EU_R0603"))
    )
    (comp (ref "R232")
      (value "68R")
      (footprint "eagle-import:R0603")
      (libsource (lib "eagle-import") (part "R-EU_R0603"))
    )
    (comp (ref "R233")
      (value "68R")
      (footprint "eagle-import:R0603")
      (libsource (lib "eagle-import") (part "R-EU_R0603"))
    )
    (comp (ref "R234")
      (value "68R")
      (footprint "eagle-import:R0603")
      (libsource (lib "eagle-import") (part "R-EU_R0603"))
    )
    (comp (ref "R241")
      (value "68R")
      (footprint "eagle-import:R0603")
      (libsource (lib "eagle-import") (part "R-EU_R0603"))
    )
    (comp (ref "R251")
      (value "68R")
      (footprint "eagle-import:R0603")
      (libsource (lib "eagle-import") (part "R-EU_R0603"))
    )
    (comp (ref "R271")
      (value "R-EU_R0805")
      (footprint "eagle-import:R0805")
      (libsource (lib "eagle-import") (part "R-EU_R0805"))
    )
    (comp (ref "R281")
      (value "R-EU_R0805")
      (footprint "eagle-import:R0805")
      (libsource (lib "eagle-import") (part "R-EU_R0805"))
    )
    (comp (ref "R291")
      (value "R-EU_R0603")
      (footprint "eagle-import:R0603")
      (libsource (lib "eagle-import") (part "R-EU_R0603"))
    )
    (comp (ref "RPOLY291")
      (value "50mA/150mA")
      (footprint "eagle-import:R1210")
      (libsource (lib "eagle-import") (part "R-EU_R1210"))
    )
    (comp (ref "U201")
      (value "SIM808")
      (footprint "eagle-import:SIM808")
      (libsource (lib "eagle-import") (part "SIM808"))
    )
    (comp (ref "X291")
      (value "MCX-J-P-X-RA-SM1")
      (footprint "eagle-import:MCX-J-P-X-RA-SM1")
      (libsource (lib "eagle-import") (part "MCX-J-P-X-RA-SM1"))
    )
    (comp (ref "C191")
      (value "100nF")
      (footprint "eagle-import:C0603")
      (libsource (lib "eagle-import") (part "C-EUC0603"))
    )
    (comp (ref "C192")
      (value "100nF")
      (footprint "eagle-import:C0603")
      (libsource (lib "eagle-import") (part "C-EUC0603"))
    )
    (comp (ref "C193")
      (value "100nF")
      (footprint "eagle-import:C0603")
      (libsource (lib "eagle-import") (part "C-EUC0603"))
    )
    (comp (ref "C194")
      (value "100nF")
      (footprint "eagle-import:C0603")
      (libsource (lib "eagle-import") (part "C-EUC0603"))
    )
    (comp (ref "C195")
      (value "100nF")
      (footprint "eagle-import:C0603")
      (libsource (lib "eagle-import") (part "C-EUC0603"))
    )
    (comp (ref "C196")
      (value "100nF")
      (footprint "eagle-import:C0603")
      (libsource (lib "eagle-import") (part "C-EUC0603"))
    )
    (comp (ref "C1111")
      (value "47uF")
      (footprint "eagle-import:C0805")
      (libsource (lib "eagle-import") (part "C-EUC0805"))
    )
    (comp (ref "C1112")
      (value "100nF")
      (footprint "eagle-import:C0603")
      (libsource (lib "eagle-import") (part "C-EUC0603"))
    )
    (comp (ref "C1113")
      (value "47uF")
      (footprint "eagle-import:C0805")
      (libsource (lib "eagle-import") (part "C-EUC0805"))
    )
    (comp (ref "C1121")
      (value "100nF")
      (footprint "eagle-import:C0603")
      (libsource (lib "eagle-import") (part "C-EUC0603"))
    )
    (comp (ref "C1141")
      (value "100pF")
      (footprint "eagle-import:C0603")
      (libsource (lib "eagle-import") (part "C-EUC0603"))
    )
    (comp (ref "D1111")
      (value "CRS08")
      (footprint "eagle-import:SOD80C")
      (libsource (lib "eagle-import") (part "CRS08"))
    )
    (comp (ref "D1121")
      (value "CRS08")
      (footprint "eagle-import:SOD80C")
      (libsource (lib "eagle-import") (part "CRS08"))
    )
    (comp (ref "D1122")
      (value "CRS08")
      (footprint "eagle-import:SOD80C")
      (libsource (lib "eagle-import") (part "CRS08"))
    )
    (comp (ref "L191")
      (value "10uH")
      (footprint "eagle-import:R0603")
      (libsource (lib "eagle-import") (part "R-EU_R0603"))
    )
    (comp (ref "L1111")
      (value "4.7uH")
      (footprint "eagle-import:L5650M")
      (libsource (lib "eagle-import") (part "L-EUL5650M"))
    )
    (comp (ref "R1111")
      (value "4.02kR")
      (footprint "eagle-import:R0603")
      (libsource (lib "eagle-import") (part "R-EU_R0603"))
    )
    (comp (ref "R1112")
      (value "6.04kR")
      (footprint "eagle-import:R0603")
      (libsource (lib "eagle-import") (part "R-EU_R0603"))
    )
    (comp (ref "R1113")
      (value "100kR")
      (footprint "eagle-import:R0603")
      (libsource (lib "eagle-import") (part "R-EU_R0603"))
    )
    (comp (ref "R1114")
      (value "15kR")
      (footprint "eagle-import:R0603")
      (libsource (lib "eagle-import") (part "R-EU_R0603"))
    )
    (comp (ref "R1115")
      (value "68kR")
      (footprint "eagle-import:R0603")
      (libsource (lib "eagle-import") (part "R-EU_R0603"))
    )
    (comp (ref "R1131")
      (value "4.02kR")
      (footprint "eagle-import:R0603")
      (libsource (lib "eagle-import") (part "R-EU_R0603"))
    )
    (comp (ref "R1132")
      (value "6.04kR")
      (footprint "eagle-import:R0603")
      (libsource (lib "eagle-import") (part "R-EU_R0603"))
    )
    (comp (ref "R1142")
      (value "2.0kR")
      (footprint "eagle-import:R0603")
      (libsource (lib "eagle-import") (part "R-EU_R0603"))
    )
    (comp (ref "U1111")
      (value "LM2831YMF")
      (footprint "eagle-import:SOT95P280X145-5N")
      (fields (field (name "MPN") "LM2831YMF/NOPB"))
      (libsource (lib "eagle-import") (part "LM2831YMF"))
    )
    (comp (ref "U1121")
      (value "LM4120IM5-3.0")
      (footprint "eagle-import:SOT95P285X120-5N")
      (libsource (lib "eagle-import") (part "LM4120IM5-3.0"))
    )
  )
  (nets
    (net (code "1") (name "+3V0") (class "Default")
      (node (ref "C1002") (pin "1") (pinfunction "1_1") (pintype "passive"))
      (node (ref "C101") (pin "1") (pinfunction "1_1") (pintype "passive"))
      (node (ref "C251") (pin "1") (pinfunction "1_1") (pintype "passive"))
      (node (ref "R1142") (pin "2") (pinfunction "2_2") (pintype "passive"))
      (node (ref "U1001") (pin "4") (pinfunction "VCC_3V0_4") (pintype "power_in"))
      (node (ref "U101") (pin "51") (pinfunction "VBAT_51") (pintype "power_in"))
      (node (ref "U1121") (pin "5") (pinfunction "VOUT_5") (pintype "power_in"))
      (node (ref "U201") (pin "17") (pinfunction "VRTC_17") (pintype "power_in"))
    )
    (net (code "2") (name "+3V3") (class "Default")
      (node (ref "C1012") (pin "1") (pinfunction "1_1") (pintype "passive"))
      (node (ref "C1112") (pin "1") (pinfunction "1_1") (pintype "passive"))
      (node (ref "C1113") (pin "1") (pinfunction "1_1") (pintype "passive"))
      (node (ref "C191") (pin "1") (pinfunction "1_1") (pintype "passive"))
      (node (ref "C192") (pin "1") (pinfunction "1_1") (pintype "passive"))
      (node (ref "C193") (pin "1") (pinfunction "1_1") (pintype "passive"))
      (node (ref "C194") (pin "1") (pinfunction "1_1") (pintype "passive"))
      (node (ref "C195") (pin "1") (pinfunction "1_1") (pintype "passive"))
      (node (ref "C301") (pin "1") (pinfunction "1_1") (pintype "passive"))
      (node (ref "C302") (pin "1") (pinfunction "1_1") (pintype "passive"))
      (node (ref "C401") (pin "1") (pinfunction "1_1") (pintype "passive"))
      (node (ref "C501") (pin "1") (pinfunction "1_1") (pintype "passive"))
      (node (ref "C601") (pin "1") (pinfunction "1_1") (pintype "passive"))
      (node (ref "L1111") (pin "1") (pinfunction "1_1") (pintype "passive"))
      (node (ref "L191") (pin "2") (pinfunction "2_2") (pintype "passive"))
      (node (ref "R1012") (pin "2") (pinfunction "2_2") (pintype "passive"))
      (node (ref "R111") (pin "2") (pinfunction "2_2") (pintype "passive"))
      (node (ref "R1115") (pin "2") (pinfunction "2_2") (pintype "passive"))
      (node (ref "R112") (pin "2") (pinfunction "2_2") (pintype "passive"))
      (node (ref "R211") (pin "1") (pinfunction "1_1") (pintype "passive"))
      (node (ref "R212") (pin "1") (pinfunction "1_1") (pintype "passive"))
      (node (ref "R401") (pin "2") (pinfunction "2_2") (pintype "passive"))
      (node (ref "R402") (pin "2") (pinfunction "2_2") (pintype "passive"))
      (node (ref "RPOLY291") (pin "2") (pinfunction "2_2") (pintype "passive"))
      (node (ref "U101") (pin "15") (pinfunction "VCC_1_15") (pintype "power_in"))
      (node (ref "U101") (pin "25") (pinfunction "VCC_2_25") (pintype "power_in"))
      (node (ref "U101") (pin "35") (pinfunction "VCC_3_35") (pintype "power_in"))
      (node (ref "U101") (pin "45") (pinfunction "VCC_4_45") (pintype "power_in"))
      (node (ref "U101") (pin "53") (pinfunction "VCC_5_53") (pintype "power_in"))
      (node (ref "U1011") (pin "5") (pinfunction "V+_5") (pintype "power_in"))
      (node (ref "U1021") (pin "5") (pinfunction "V+_5") (pintype "power_in"))
      (node (ref "U301") (pin "1") (pinfunction "VDDIO_1") (pintype "power_in"))
      (node (ref "U301") (pin "13") (pinfunction "VDD_13") (pintype "power_in"))
      (node (ref "U301") (pin "22") (pinfunction "~{CS}_22") (pintype "input"))
      (node (ref "U301") (pin "8") (pinfunction "VDDIO_8") (pintype "power_in"))
      (node (ref "U401") (pin "1") (pinfunction "VDD_1") (pintype "power_in"))
      (node (ref "U401") (pin "2") (pinfunction "PS_2") (pintype "input"))
      (node (ref "U401") (pin "4") (pinfunction "CSB_~{ADDR}_4") (pintype "input"))
      (node (ref "U501") (pin "5") (pinfunction "VDD_5") (pintype "power_in"))
      (node (ref "U601") (pin "16") (pinfunction "VDD_IO_16") (pintype "power_in"))
      (node (ref "X111") (pin "7") (pinfunction "7_7") (pintype "passive"))
      (node (ref "X121") (pin "5") (pinfunction "5_5") (pintype "passive"))
      (node (ref "X131") (pin "2") (pinfunction "2_2") (pintype "passive"))
    )
    (net (code "3") (name "+5V") (class "Default")
      (node (ref "C711") (pin "1") (pinfunction "1_1") (pintype "passive"))
      (node (ref "C712") (pin "1") (pinfunction "1_1") (pintype "passive"))
      (node (ref "D1121") (pin "A") (pinfunction "A_A") (pintype "passive"))
      (node (ref "JP201") (pin "1") (pinfunction "1_1") (pintype "passive"))
      (node (ref "R1112") (pin "2") (pinfunction "2_2") (pintype "passive"))
      (node (ref "RPOLY711") (pin "2") (pinfunction "2_2") (pintype "passive"))
      (node (ref "X121") (pin "3") (pinfunction "3_3") (pintype "passive"))
    )
    (net (code "4") (name "AD_5V0") (class "Default")
      (node (ref "R1111") (pin "2") (pinfunction "2_2") (pintype "passive"))
      (node (ref "R1112") (pin "1") (pinfunction "1_1") (pintype "passive"))
      (node (ref "U101") (pin "64") (pinfunction "PA2_64") (pintype "bidirectional"))
    )
    (net (code "5") (name "AD_VBAT") (class "Default")
      (node (ref "R1131") (pin "1") (pinfunction "1_1") (pintype "passive"))
      (node (ref "R1132") (pin "2") (pinfunction "2_2") (pintype "passive"))
      (node (ref "U101") (pin "1") (pinfunction "PA3_1") (pintype "bidirectional"))
    )
    (net (code "6") (name "AD_VCTCXO") (class "Default")
      (node (ref "R1021") (pin "2") (pinfunction "2_2") (pintype "passive"))
      (node (ref "U101") (pin "63") (pinfunction "PA1_63") (pintype "bidirectional"))
      (node (ref "U1021") (pin "1") (pinfunction "OUT_1") (pintype "output"))
    )
    (net (code "7") (name "AREFA") (class "Default")
      (node (ref "C1141") (pin "1") (pinfunction "1_1") (pintype "passive"))
      (node (ref "R1142") (pin "1") (pinfunction "1_1") (pintype "passive"))
      (node (ref "U101") (pin "62") (pinfunction "PA0_62") (pintype "bidirectional"))
    )
    (net (code "8") (name "AVCC") (class "Default")
      (node (ref "C196") (pin "1") (pinfunction "1_1") (pintype "passive"))
      (node (ref "L191") (pin "1") (pinfunction "1_1") (pintype "passive"))
      (node (ref "U101") (pin "61") (pinfunction "AVCC_61") (pintype "power_in"))
    )
    (net (code "9") (name "AX_ANT") (class "Default")
      (node (ref "C686") (pin "2") (pinfunction "2_2") (pintype "passive"))
      (node (ref "L682") (pin "2") (pinfunction "2_2") (pintype "passive"))
      (node (ref "X685") (pin "1") (pinfunction "1_1") (pintype "passive"))
    )
    (net (code "10") (name "AX_ANTN") (class "Default")
      (node (ref "C686") (pin "1") (pinfunction "1_1") (pintype "passive"))
      (node (ref "L686") (pin "2") (pinfunction "2_2") (pintype "passive"))
      (node (ref "U601") (pin "4") (pinfunction "ANTN_4") (pintype "passive"))
    )
    (net (code "11") (name "AX_ANTP") (class "Default")
      (node (ref "C681") (pin "1") (pinfunction "1_1") (pintype "passive"))
      (node (ref "L681") (pin "1") (pinfunction "1_1") (pintype "passive"))
      (node (ref "U601") (pin "3") (pinfunction "ANTP_3") (pintype "passive"))
    )
    (net (code "12") (name "AX_ANT_I") (class "Default")
      (node (ref "C681") (pin "2") (pinfunction "2_2") (pintype "passive"))
      (node (ref "L682") (pin "1") (pinfunction "1_1") (pintype "passive"))
    )
    (net (code "13") (name "AX_CLK") (class "Default")
      (node (ref "U101") (pin "23") (pinfunction "PC7_23") (pintype "bidirectional"))
      (node (ref "U601") (pin "11") (pinfunction "CLK_11") (pintype "input"))
    )
    (net (code "14") (name "AX_IRQ") (class "Default")
      (node (ref "U101") (pin "19") (pinfunction "PC3_19") (pintype "bidirectional"))
      (node (ref "U601") (pin "14") (pinfunction "IRQ_14") (pintype "bidirectional"))
    )
    (net (code "15") (name "AX_L1") (class "Default")
      (node (ref "L671") (pin "1") (pinfunction "1_1") (pintype "passive"))
      (node (ref "U601") (pin "8") (pinfunction "L1_8") (pintype "passive"))
    )
    (net (code "16") (name "AX_L2") (class "Default")
      (node (ref "L671") (pin "2") (pinfunction "2_2") (pintype "passive"))
      (node (ref "U601") (pin "7") (pinfunction "L2_7") (pintype "passive"))
    )
    (net (code "17") (name "AX_MISO") (class "Default")
      (node (ref "U101") (pin "22") (pinfunction "PC6_22") (pintype "bidirectional"))
      (node (ref "U601") (pin "12") (pinfunction "MISO_12") (pintype "output"))
    )
    (net (code "18") (name "AX_MOSI") (class "Default")
      (node (ref "U101") (pin "21") (pinfunction "PC5_21") (pintype "bidirectional"))
      (node (ref "U601") (pin "13") (pinfunction "MOSI_13") (pintype "input"))
    )
    (net (code "19") (name "AX_SEL") (class "Default")
      (node (ref "U101") (pin "20") (pinfunction "PC4_20") (pintype "bidirectional"))
      (node (ref "U601") (pin "10") (pinfunction "SEL_10") (pintype "input"))
    )
    (net (code "20") (name "BT_ANT") (class "Default")
      (node (ref "C282") (pin "1") (pinfunction "1_1") (pintype "passive"))
      (node (ref "R281") (pin "2") (pinfunction "2_2") (pintype "passive"))
    )
    (net (code "21") (name "BT_RF") (class "Default")
      (node (ref "C281") (pin "1") (pinfunction "1_1") (pintype "passive"))
      (node (ref "R281") (pin "1") (pinfunction "1_1") (pintype "passive"))
      (node (ref "U201") (pin "53") (pinfunction "ANT_BT_53") (pintype "bidirectional"))
    )
    (net (code "22") (name "CTS1") (class "Default")
      (node (ref "R223") (pin "1") (pinfunction "1_1") (pintype "passive"))
      (node (ref "U101") (pin "54") (pinfunction "PF6_54") (pintype "bidirectional"))
    )
    (net (code "23") (name "DCD1") (class "Default")
      (node (ref "R222") (pin "1") (pinfunction "1_1") (pintype "passive"))
      (node (ref "U101") (pin "46") (pinfunction "PF0_46") (pintype "bidirectional"))
    )
    (net (code "24") (name "DTR1") (class "Default")
      (node (ref "R171") (pin "1") (pinfunction "1_1") (pintype "passive"))
      (node (ref "U101") (pin "47") (pinfunction "PF1_47") (pintype "bidirectional"))
    )
    (net (code "25") (name "EN") (class "Default")
      (node (ref "R1113") (pin "2") (pinfunction "2_2") (pintype "passive"))
      (node (ref "U1111") (pin "4") (pinfunction "EN_4") (pintype "input"))
    )
    (net (code "26") (name "FB") (class "Default")
      (node (ref "R1114") (pin "2") (pinfunction "2_2") (pintype "passive"))
      (node (ref "R1115") (pin "1") (pinfunction "1_1") (pintype "passive"))
      (node (ref "U1111") (pin "3") (pinfunction "FB_3") (pintype "input"))
    )
    (net (code "27") (name "GND") (class "Default")
      (node (ref "C1001") (pin "2") (pinfunction "2_2") (pintype "passive"))
      (node (ref "C1002") (pin "2") (pinfunction "2_2") (pintype "passive"))
      (node (ref "C101") (pin "2") (pinfunction "2_2") (pintype "passive"))
      (node (ref "C1011") (pin "2") (pinfunction "2_2") (pintype "passive"))
      (node (ref "C1012") (pin "2") (pinfunction "2_2") (pintype "passive"))
      (node (ref "C1111") (pin "2") (pinfunction "2_2") (pintype "passive"))
      (node (ref "C1112") (pin "2") (pinfunction "2_2") (pintype "passive"))
      (node (ref "C1113") (pin "2") (pinfunction "2_2") (pintype "passive"))
      (node (ref "C1121") (pin "2") (pinfunction "2_2") (pintype "passive"))
      (node (ref "C1141") (pin "2") (pinfunction "2_2") (pintype "passive"))
      (node (ref "C141") (pin "2") (pinfunction "2_2") (pintype "passive"))
      (node (ref "C191") (pin "2") (pinfunction "2_2") (pintype "passive"))
      (node (ref "C192") (pin "2") (pinfunction "2_2") (pintype "passive"))
      (node (ref "C193") (pin "2") (pinfunction "2_2") (pintype "passive"))
      (node (ref "C194") (pin "2") (pinfunction "2_2") (pintype "passive"))
      (node (ref "C195") (pin "2") (pinfunction "2_2") (pintype "passive"))
      (node (ref "C196") (pin "2") (pinfunction "2_2") (pintype "passive"))
      (node (ref "C201") (pin "2") (pinfunction "2_2") (pintype "passive"))
      (node (ref "C251") (pin "2") (pinfunction "2_2") (pintype "passive"))
      (node (ref "C271") (pin "2") (pinfunction "2_2") (pintype "passive"))
      (node (ref "C272") (pin "2") (pinfunction "2_2") (pintype "passive"))
      (node (ref "C281") (pin "2") (pinfunction "2_2") (pintype "passive"))
      (node (ref "C282") (pin "2") (pinfunction "2_2") (pintype "passive"))
      (node (ref "C291") (pin "2") (pinfunction "2_2") (pintype "passive"))
      (node (ref "C292") (pin "2") (pinfunction "2_2") (pintype "passive"))
      (node (ref "C301") (pin "2") (pinfunction "2_2") (pintype "passive"))
      (node (ref "C302") (pin "2") (pinfunction "2_2") (pintype "passive"))
      (node (ref "C303") (pin "2") (pinfunction "2_2") (pintype "passive"))
      (node (ref "C401") (pin "2") (pinfunction "2_2") (pintype "passive"))
      (node (ref "C501") (pin "2") (pinfunction "2_2") (pintype "passive"))
      (node (ref "C601") (pin "2") (pinfunction "2_2") (pintype "passive"))
      (node (ref "C611") (pin "2") (pinfunction "2_2") (pintype "passive"))
      (node (ref "C612") (pin "2") (pinfunction "2_2") (pintype "passive"))
      (node (ref "C701") (pin "2") (pinfunction "2_2") (pintype "passive"))
      (node (ref "C711") (pin "2") (pinfunction "2_2") (pintype "passive"))
      (node (ref "C712") (pin "2") (pinfunction "2_2") (pintype "passive"))
      (node (ref "C901") (pin "2") (pinfunction "2_2") (pintype "passive"))
      (node (ref "D1111") (pin "A") (pinfunction "A_A") (pintype "passive"))
      (node (ref "D201") (pin "A") (pinfunction "A_A") (pintype "passive"))
      (node (ref "D721") (pin "A") (pinfunction "A_A") (pintype "passive"))
      (node (ref "D722") (pin "A") (pinfunction "A_A") (pintype "passive"))
      (node (ref "H1201") (pin "B2,8") (pinfunction "MOUNT_B2,8") (pintype "passive"))
      (node (ref "H1203") (pin "B2,8") (pinfunction "MOUNT_B2,8") (pintype "passive"))
      (node (ref "H1204") (pin "B2,8") (pinfunction "MOUNT_B2,8") (pintype "passive"))
      (node (ref "L681") (pin "2") (pinfunction "2_2") (pintype "passive"))
      (node (ref "L686") (pin "1") (pinfunction "1_1") (pintype "passive"))
      (node (ref "Q651") (pin "2") (pinfunction "3_2") (pintype "passive"))
      (node (ref "Q651") (pin "4") (pinfunction "3_4") (pintype "passive"))
      (node (ref "R1011") (pin "1") (pinfunction "1_1") (pintype "passive"))
      (node (ref "R1111") (pin "1") (pinfunction "1_1") (pintype "passive"))
      (node (ref "R1114") (pin "1") (pinfunction "1_1") (pintype "passive"))
      (node (ref "R1131") (pin "2") (pinfunction "2_2") (pintype "passive"))
      (node (ref "R701") (pin "2") (pinfunction "2_2") (pintype "passive"))
      (node (ref "R724") (pin "2") (pinfunction "2_2") (pintype "passive"))
      (node (ref "U1001") (pin "2") (pinfunction "GND_2") (pintype "power_in"))
      (node (ref "U101") (pin "14") (pinfunction "GND_1_14") (pintype "passive"))
      (node (ref "U101") (pin "24") (pinfunction "GND_2_24") (pintype "passive"))
      (node (ref "U101") (pin "34") (pinfunction "GND_3_34") (pintype "passive"))
      (node (ref "U101") (pin "44") (pinfunction "GND_4_44") (pintype "passive"))
      (node (ref "U101") (pin "52") (pinfunction "GND_5_52") (pintype "passive"))
      (node (ref "U101") (pin "60") (pinfunction "GND_6_60") (pintype "passive"))
      (node (ref "U1011") (pin "2") (pinfunction "V-_2") (pintype "power_in"))
      (node (ref "U1021") (pin "2") (pinfunction "V-_2") (pintype "power_in"))
      (node (ref "U1111") (pin "2") (pinfunction "GND_2") (pintype "passive"))
      (node (ref "U1121") (pin "2") (pinfunction "GND_2") (pintype "passive"))
      (node (ref "U201") (pin "1") (pinfunction "GND_1") (pintype "power_in"))
      (node (ref "U201") (pin "18") (pinfunction "GND_18") (pintype "power_in"))
      (node (ref "U201") (pin "2") (pinfunction "GND_2") (pintype "power_in"))
      (node (ref "U201") (pin "28") (pinfunction "GND_28") (pintype "power_in"))
      (node (ref "U201") (pin "3") (pinfunction "GND_3") (pintype "power_in"))
      (node (ref "U201") (pin "34") (pinfunction "GND_34") (pintype "power_in"))
      (node (ref "U201") (pin "36") (pinfunction "GND_36") (pintype "power_in"))
      (node (ref "U201") (pin "40") (pinfunction "GND_40") (pintype "power_in"))
      (node (ref "U201") (pin "51") (pinfunction "GND_51") (pintype "power_in"))
      (node (ref "U201") (pin "52") (pinfunction "GND_52") (pintype "power_in"))
      (node (ref "U201") (pin "54") (pinfunction "GND_54") (pintype "power_in"))
      (node (ref "U201") (pin "64") (pinfunction "GND_64") (pintype "power_in"))
      (node (ref "U201") (pin "65") (pinfunction "GND_65") (pintype "power_in"))
      (node (ref "U201") (pin "67") (pinfunction "GND_67") (pintype "power_in"))
      (node (ref "U201") (pin "68") (pinfunction "GND_68") (pintype "power_in"))
      (node (ref "U301") (pin "11") (pinfunction "FSYNC_11") (pintype "passive"))
      (node (ref "U301") (pin "18") (pinfunction "GND_18") (pintype "passive"))
      (node (ref "U301") (pin "20") (pinfunction "GND_20") (pintype "passive"))
      (node (ref "U301") (pin "9") (pinfunction "AD0/SDO_9") (pintype "bidirectional"))
      (node (ref "U401") (pin "3") (pinfunction "GND_3") (pintype "passive"))
      (node (ref "U501") (pin "2") (pinfunction "ADDR_2") (pintype "input"))
      (node (ref "U501") (pin "7") (pinfunction "R_7") (pintype "passive"))
      (node (ref "U501") (pin "8") (pinfunction "VSS_8") (pintype "passive"))
      (node (ref "U501") (pin "9") (pinfunction "PAD_9") (pintype "passive"))
      (node (ref "U601") (pin "17") (pinfunction "GPADC1_17") (pintype "passive"))
      (node (ref "U601") (pin "18") (pinfunction "GPADC2_18") (pintype "passive"))
      (node (ref "U601") (pin "2") (pinfunction "GND_2") (pintype "power_in"))
      (node (ref "U601") (pin "21") (pinfunction "GND_21") (pintype "power_in"))
      (node (ref "X111") (pin "10") (pinfunction "10_10") (pintype "passive"))
      (node (ref "X111") (pin "2") (pinfunction "2_2") (pintype "passive"))
      (node (ref "X121") (pin "1") (pinfunction "1_1") (pintype "passive"))
      (node (ref "X121") (pin "6") (pinfunction "6_6") (pintype "passive"))
      (node (ref "X131") (pin "6") (pinfunction "6_6") (pintype "passive"))
      (node (ref "X181") (pin "1") (pinfunction "1_1") (pintype "passive"))
      (node (ref "X291") (pin "2") (pinfunction "2_2") (pintype "passive"))
      (node (ref "X291") (pin "3") (pinfunction "3_3") (pintype "passive"))
      (node (ref "X291") (pin "4") (pinfunction "4_4") (pintype "passive"))
      (node (ref "X291") (pin "5") (pinfunction "5_5") (pintype "passive"))
      (node (ref "X685") (pin "2") (pinfunction "2_2") (pintype "passive"))
      (node (ref "X685") (pin "3") (pinfunction "2_3") (pintype "passive"))
      (node (ref "X685") (pin "4") (pinfunction "2_4") (pintype "passive"))
      (node (ref "X685") (pin "5") (pinfunction "2_5") (pintype "passive"))
      (node (ref "X701") (pin "GND") (pinfunction "GND_GND") (pintype "passive"))
      (node (ref "X801") (pin "G1") (pinfunction "SHIELD_G1") (pintype "passive"))
      (node (ref "X801") (pin "G2") (pinfunction "SHIELD_G2") (pintype "passive"))
      (node (ref "X801") (pin "G3") (pinfunction "SHIELD_G3") (pintype "passive"))
      (node (ref "X801") (pin "G4") (pinfunction "SHIELD_G4") (pintype "passive"))
      (node (ref "X801") (pin "G5") (pinfunction "SHIELD_G5") (pintype "passive"))
      (node (ref "X801") (pin "G6") (pinfunction "SHIELD_G6") (pintype "passive"))
      (node (ref "X801") (pin "G7") (pinfunction "SHIELD_G7") (pintype "passive"))
      (node (ref "X801") (pin "G8") (pinfunction "SHIELD_G8") (pintype "passive"))
      (node (ref "X801") (pin "S5") (pinfunction "S5_S5") (pintype "passive"))
      (node (ref "X801") (pin "T6") (pinfunction "T6_T6") (pintype "passive"))
      (node (ref "X901") (pin "3") (pinfunction "3_3") (pintype "passive"))
    )
    (net (code "28") (name "GPS_1PPS") (class "Default")
      (node (ref "R251") (pin "1") (pinfunction "1_1") (pintype "passive"))
      (node (ref "U101") (pin "58") (pinfunction "PR0_58") (pintype "bidirectional"))
    )
    (net (code "29") (name "GPS_1PPS_DRV") (class "Default")
      (node (ref "R251") (pin "2") (pinfunction "2_2") (pintype "passive"))
      (node (ref "U201") (pin "37") (pinfunction "1PPS_37") (pintype "output"))
    )
    (net (code "30") (name "GPS_ANT") (class "Default")
      (node (ref "C291") (pin "1") (pinfunction "1_1") (pintype "passive"))
      (node (ref "L291") (pin "2") (pinfunction "2_2") (pintype "passive"))
      (node (ref "R291") (pin "1") (pinfunction "1_1") (pintype "passive"))
      (node (ref "X291") (pin "1") (pinfunction "1_1") (pintype "passive"))
    )
    (net (code "31") (name "GPS_PWR") (class "Default")
      (node (ref "L291") (pin "1") (pinfunction "1_1") (pintype "passive"))
      (node (ref "RPOLY291") (pin "1") (pinfunction "1_1") (pintype "passive"))
    )
    (net (code "32") (name "GPS_RF_IN") (class "Default")
      (node (ref "C292") (pin "1") (pinfunction "1_1") (pintype "passive"))
      (node (ref "R291") (pin "2") (pinfunction "2_2") (pintype "passive"))
      (node (ref "U201") (pin "35") (pinfunction "GPS_RF_IN_35") (pintype "input"))
    )
    (net (code "33") (name "GSM_ANT") (class "Default")
      (node (ref "C272") (pin "1") (pinfunction "1_1") (pintype "passive"))
      (node (ref "R271") (pin "2") (pinfunction "2_2") (pintype "passive"))
    )
    (net (code "34") (name "GSM_CTS") (class "Default")
      (node (ref "R223") (pin "2") (pinfunction "2_2") (pintype "passive"))
      (node (ref "U201") (pin "12") (pinfunction "CTS_12") (pintype "output"))
    )
    (net (code "35") (name "GSM_DCD") (class "Default")
      (node (ref "R222") (pin "2") (pinfunction "2_2") (pintype "passive"))
      (node (ref "U201") (pin "11") (pinfunction "DCD_11") (pintype "output"))
    )
    (net (code "36") (name "GSM_DTR") (class "Default")
      (node (ref "R171") (pin "2") (pinfunction "2_2") (pintype "passive"))
      (node (ref "U201") (pin "9") (pinfunction "DTR_9") (pintype "input"))
    )
    (net (code "37") (name "GSM_NETLIGHT") (class "Default")
      (node (ref "R231") (pin "2") (pinfunction "2_2") (pintype "passive"))
      (node (ref "U101") (pin "5") (pinfunction "PA7_5") (pintype "bidirectional"))
    )
    (net (code "38") (name "GSM_NETLIGHT_DRV") (class "Default")
      (node (ref "R231") (pin "1") (pinfunction "1_1") (pintype "passive"))
      (node (ref "U201") (pin "50") (pinfunction "NETLIGHT_50") (pintype "output"))
    )
    (net (code "39") (name "GSM_PCM_CLK") (class "Default")
      (node (ref "R141") (pin "2") (pinfunction "2_2") (pintype "passive"))
      (node (ref "U201") (pin "46") (pinfunction "PCM_CLK_46") (pintype "input"))
    )
    (net (code "40") (name "GSM_PCM_CLK_DRV") (class "Default")
      (node (ref "R141") (pin "1") (pinfunction "1_1") (pintype "passive"))
      (node (ref "U101") (pin "27") (pinfunction "PD1_27") (pintype "bidirectional"))
    )
    (net (code "41") (name "GSM_PCM_IN") (class "Default")
      (node (ref "R142") (pin "2") (pinfunction "2_2") (pintype "passive"))
      (node (ref "U201") (pin "47") (pinfunction "PCM_IN_47") (pintype "input"))
    )
    (net (code "42") (name "GSM_PCM_IN_DRV") (class "Default")
      (node (ref "R142") (pin "1") (pinfunction "1_1") (pintype "passive"))
      (node (ref "U101") (pin "29") (pinfunction "PD3_29") (pintype "bidirectional"))
    )
    (net (code "43") (name "GSM_PCM_OUT") (class "Default")
      (node (ref "R233") (pin "2") (pinfunction "2_2") (pintype "passive"))
      (node (ref "U101") (pin "28") (pinfunction "PD2_28") (pintype "bidirectional"))
    )
    (net (code "44") (name "GSM_PCM_OUT_DRV") (class "Default")
      (node (ref "R233") (pin "1") (pinfunction "1_1") (pintype "passive"))
      (node (ref "U201") (pin "48") (pinfunction "PCM_OUT_48") (pintype "output"))
    )
    (net (code "45") (name "GSM_PCM_SYNC") (class "Default")
      (node (ref "R234") (pin "2") (pinfunction "2_2") (pintype "passive"))
      (node (ref "U101") (pin "26") (pinfunction "PD0_26") (pintype "bidirectional"))
    )
    (net (code "46") (name "GSM_PCM_SYNC_DRV") (class "Default")
      (node (ref "R234") (pin "1") (pinfunction "1_1") (pintype "passive"))
      (node (ref "U201") (pin "45") (pinfunction "PCM_SYNC_45") (pintype "output"))
    )
    (net (code "47") (name "GSM_PWRKEY") (class "Default")
      (node (ref "R162") (pin "2") (pinfunction "2_2") (pintype "passive"))
      (node (ref "U201") (pin "8") (pinfunction "PWRKEY_8") (pintype "input"))
    )
    (net (code "48") (name "GSM_RESET") (class "Default")
      (node (ref "R163") (pin "2") (pinfunction "2_2") (pintype "passive"))
      (node (ref "U201") (pin "16") (pinfunction "RESET_16") (pintype "input"))
    )
    (net (code "49") (name "GSM_RF") (class "Default")
      (node (ref "C271") (pin "1") (pinfunction "1_1") (pintype "passive"))
      (node (ref "R271") (pin "1") (pinfunction "1_1") (pintype "passive"))
      (node (ref "U201") (pin "66") (pinfunction "GSM_RF_IN_66") (pintype "bidirectional"))
    )
    (net (code "50") (name "GSM_RF_SYNC") (class "Default")
      (node (ref "C141") (pin "1") (pinfunction "1_1") (pintype "passive"))
      (node (ref "R241") (pin "2") (pinfunction "2_2") (pintype "passive"))
      (node (ref "U101") (pin "4") (pinfunction "PA6_4") (pintype "bidirectional"))
    )
    (net (code "51") (name "GSM_RF_SYNC_DRV") (class "Default")
      (node (ref "R241") (pin "1") (pinfunction "1_1") (pintype "passive"))
      (node (ref "U201") (pin "63") (pinfunction "RF_SYNC_63") (pintype "output"))
    )
    (net (code "52") (name "GSM_RI") (class "Default")
      (node (ref "R221") (pin "2") (pinfunction "2_2") (pintype "passive"))
      (node (ref "U201") (pin "10") (pinfunction "RI_10") (pintype "output"))
    )
    (net (code "53") (name "GSM_RTS") (class "Default")
      (node (ref "R173") (pin "2") (pinfunction "2_2") (pintype "passive"))
      (node (ref "U201") (pin "13") (pinfunction "RTS_13") (pintype "input"))
    )
    (net (code "54") (name "GSM_RXD") (class "Default")
      (node (ref "R172") (pin "2") (pinfunction "2_2") (pintype "passive"))
      (node (ref "U201") (pin "15") (pinfunction "RXD_15") (pintype "input"))
    )
    (net (code "55") (name "GSM_STATUS") (class "Default")
      (node (ref "R232") (pin "2") (pinfunction "2_2") (pintype "passive"))
      (node (ref "U101") (pin "38") (pinfunction "PE2_38") (pintype "bidirectional"))
    )
    (net (code "56") (name "GSM_STATUS_DRV") (class "Default")
      (node (ref "R232") (pin "1") (pinfunction "1_1") (pintype "passive"))
      (node (ref "U201") (pin "49") (pinfunction "STATUS_49") (pintype "output"))
    )
    (net (code "57") (name "GSM_TXD") (class "Default")
      (node (ref "R224") (pin "2") (pinfunction "2_2") (pintype "passive"))
      (node (ref "U201") (pin "14") (pinfunction "TXD_14") (pintype "output"))
    )
    (net (code "58") (name "GSM_VDD_EXT") (class "Default")
      (node (ref "R161") (pin "2") (pinfunction "2_2") (pintype "passive"))
      (node (ref "U201") (pin "7") (pinfunction "VDD_EXT(2.8VOUT)_7") (pintype "output"))
    )
    (net (code "59") (name "I2C2_INT") (class "Default")
      (node (ref "R301") (pin "2") (pinfunction "2_2") (pintype "passive"))
      (node (ref "U101") (pin "6") (pinfunction "PB0_6") (pintype "bidirectional"))
    )
    (net (code "60") (name "IO_ADC4") (class "Default")
      (node (ref "U101") (pin "2") (pinfunction "PA4_2") (pintype "bidirectional"))
      (node (ref "X181") (pin "3") (pinfunction "3_3") (pintype "passive"))
    )
    (net (code "61") (name "IO_ADC5") (class "Default")
      (node (ref "U101") (pin "3") (pinfunction "PA5_3") (pintype "bidirectional"))
      (node (ref "X181") (pin "5") (pinfunction "5_5") (pintype "passive"))
    )
    (net (code "62") (name "IO_DAC0") (class "Default")
      (node (ref "U101") (pin "8") (pinfunction "PB2_8") (pintype "bidirectional"))
      (node (ref "X181") (pin "4") (pinfunction "4_4") (pintype "passive"))
    )
    (net (code "63") (name "IO_DAC1") (class "Default")
      (node (ref "U101") (pin "9") (pinfunction "PB3_9") (pintype "bidirectional"))
      (node (ref "X181") (pin "6") (pinfunction "6_6") (pintype "passive"))
    )
    (net (code "64") (name "IO_OC1A") (class "Default")
      (node (ref "U101") (pin "30") (pinfunction "PD4_30") (pintype "bidirectional"))
      (node (ref "X181") (pin "2") (pinfunction "2_2") (pintype "passive"))
    )
    (net (code "65") (name "MPU_INT") (class "Default")
      (node (ref "R301") (pin "1") (pinfunction "1_1") (pintype "passive"))
      (node (ref "U301") (pin "12") (pinfunction "INT_12") (pintype "output"))
    )
    (net (code "66") (name "Net-(C611-Pad1)") (class "Default")
      (node (ref "C611") (pin "1") (pinfunction "1_1") (pintype "passive"))
      (node (ref "U601") (pin "1") (pinfunction "VDD_ANA_1") (pintype "passive"))
    )
    (net (code "67") (name "Net-(C612-Pad1)") (class "Default")
      (node (ref "C612") (pin "1") (pinfunction "1_1") (pintype "passive"))
      (node (ref "U601") (pin "5") (pinfunction "VDD_ANA_5") (pintype "passive"))
    )
    (net (code "68") (name "Net-(C701-Pad1)") (class "Default")
      (node (ref "C701") (pin "1") (pinfunction "1_1") (pintype "passive"))
      (node (ref "R701") (pin "1") (pinfunction "1_1") (pintype "passive"))
      (node (ref "X701") (pin "JSHIELD") (pinfunction "SHIELD_JSHIELD") (pintype "passive"))
      (node (ref "X701") (pin "JSHIELD@2") (pinfunction "SHIELD_JSHIELD@2") (pintype "passive"))
      (node (ref "X701") (pin "JSHIELD@3") (pinfunction "SHIELD_JSHIELD@3") (pintype "passive"))
      (node (ref "X701") (pin "JSHIELD@4") (pinfunction "SHIELD_JSHIELD@4") (pintype "passive"))
      (node (ref "X701") (pin "JSHIELD@5") (pinfunction "SHIELD_JSHIELD@5") (pintype "passive"))
      (node (ref "X701") (pin "JSHIELD@6") (pinfunction "SHIELD_JSHIELD@6") (pintype "passive"))
    )
    (net (code "69") (name "Net-(Q651-2)") (class "Default")
      (node (ref "Q651") (pin "3") (pinfunction "2_3") (pintype "passive"))
      (node (ref "U601") (pin "19") (pinfunction "CLK16N_19") (pintype "passive"))
    )
    (net (code "70") (name "Net-(RPOLY901-Pad1)") (class "Default")
      (node (ref "RPOLY901") (pin "1") (pinfunction "1_1") (pintype "passive"))
      (node (ref "X901") (pin "1") (pinfunction "1_1") (pintype "passive"))
    )
    (net (code "71") (name "Net-(U101A-TOSC1)") (class "Default")
      (node (ref "Q101") (pin "2") (pinfunction "2_2") (pintype "passive"))
      (node (ref "U101") (pin "43") (pinfunction "TOSC1_43") (pintype "passive"))
    )
    (net (code "72") (name "Net-(U101A-TOSC2)") (class "Default")
      (node (ref "Q101") (pin "1") (pinfunction "1_1") (pintype "passive"))
      (node (ref "U101") (pin "42") (pinfunction "TOSC2_42") (pintype "passive"))
    )
    (net (code "73") (name "Net-(U301-REGOUT)") (class "Default")
      (node (ref "C303") (pin "1") (pinfunction "1_1") (pintype "passive"))
      (node (ref "U301") (pin "10") (pinfunction "REGOUT_10") (pintype "passive"))
    )
    (net (code "74") (name "Net-(U601-CLK16P)") (class "Default")
      (node (ref "Q651") (pin "1") (pinfunction "1_1") (pintype "passive"))
      (node (ref "U601") (pin "20") (pinfunction "CLK16P_20") (pintype "passive"))
    )
    (net (code "75") (name "Net-(U1021--IN)") (class "Default")
      (node (ref "R1021") (pin "1") (pinfunction "1_1") (pintype "passive"))
      (node (ref "U1021") (pin "4") (pinfunction "-IN_4") (pintype "input"))
    )
    (net (code "76") (name "Net-(U1111-VIN)") (class "Default")
      (node (ref "C1111") (pin "1") (pinfunction "1_1") (pintype "passive"))
      (node (ref "C1121") (pin "1") (pinfunction "1_1") (pintype "passive"))
      (node (ref "D1121") (pin "C") (pinfunction "C_C") (pintype "passive"))
      (node (ref "D1122") (pin "C") (pinfunction "C_C") (pintype "passive"))
      (node (ref "R1113") (pin "1") (pinfunction "1_1") (pintype "passive"))
      (node (ref "U1111") (pin "5") (pinfunction "VIN_5") (pintype "power_in"))
      (node (ref "U1121") (pin "3") (pinfunction "EN_3") (pintype "input"))
      (node (ref "U1121") (pin "4") (pinfunction "VIN_4") (pintype "power_in"))
    )
    (net (code "77") (name "Net-(X701-J_D+)") (class "Default")
      (node (ref "R723") (pin "1") (pinfunction "1_1") (pintype "passive"))
      (node (ref "R724") (pin "1") (pinfunction "1_1") (pintype "passive"))
      (node (ref "X701") (pin "D+") (pinfunction "J_D+_D+") (pintype "bidirectional"))
    )
    (net (code "78") (name "Net-(X701-J_D-)") (class "Default")
      (node (ref "R721") (pin "1") (pinfunction "1_1") (pintype "passive"))
      (node (ref "R722") (pin "1") (pinfunction "1_1") (pintype "passive"))
      (node (ref "X701") (pin "D-") (pinfunction "J_D-_D-") (pintype "bidirectional"))
    )
    (net (code "79") (name "Net-(X701-J_ID)") (class "Default")
      (node (ref "R725") (pin "1") (pinfunction "1_1") (pintype "passive"))
      (node (ref "X701") (pin "ID") (pinfunction "J_ID_ID") (pintype "bidirectional"))
    )
    (net (code "80") (name "Net-(X701-J_VUSB)") (class "Default")
      (node (ref "RPOLY711") (pin "1") (pinfunction "1_1") (pintype "passive"))
      (node (ref "X701") (pin "VBUS") (pinfunction "J_VUSB_VBUS") (pintype "power_in"))
    )
    (net (code "81") (name "PDI_CLK") (class "Default")
      (node (ref "R112") (pin "1") (pinfunction "1_1") (pintype "passive"))
      (node (ref "R132") (pin "1") (pinfunction "1_1") (pintype "passive"))
      (node (ref "X111") (pin "6") (pinfunction "6_6") (pintype "passive"))
      (node (ref "X131") (pin "5") (pinfunction "5_5") (pintype "passive"))
    )
    (net (code "82") (name "PDI_CLK_CPU") (class "Default")
      (node (ref "R132") (pin "2") (pinfunction "2_2") (pintype "passive"))
      (node (ref "U101") (pin "57") (pinfunction "~{RESET}/PDI_CLK_57") (pintype "input"))
    )
    (net (code "83") (name "PDI_DATA") (class "Default")
      (node (ref "R131") (pin "1") (pinfunction "1_1") (pintype "passive"))
      (node (ref "X131") (pin "1") (pinfunction "1_1") (pintype "passive"))
    )
    (net (code "84") (name "PDI_DATA_CPU") (class "Default")
      (node (ref "R131") (pin "2") (pinfunction "2_2") (pintype "passive"))
      (node (ref "U101") (pin "56") (pinfunction "PDI_DATA_56") (pintype "input"))
    )
    (net (code "85") (name "POWERED_GSM") (class "Default")
      (node (ref "R161") (pin "1") (pinfunction "1_1") (pintype "passive"))
      (node (ref "U101") (pin "39") (pinfunction "PE3_39") (pintype "bidirectional"))
    )
    (net (code "86") (name "PWRKEY_GSM") (class "Default")
      (node (ref "R162") (pin "1") (pinfunction "1_1") (pintype "passive"))
      (node (ref "U101") (pin "40") (pinfunction "PE4_40") (pintype "bidirectional"))
    )
    (net (code "87") (name "RESET_GSM") (class "Default")
      (node (ref "R163") (pin "1") (pinfunction "1_1") (pintype "passive"))
      (node (ref "U101") (pin "41") (pinfunction "PE5_41") (pintype "bidirectional"))
    )
    (net (code "88") (name "RI1") (class "Default")
      (node (ref "R221") (pin "1") (pinfunction "1_1") (pintype "passive"))
      (node (ref "U101") (pin "50") (pinfunction "PF4_50") (pintype "bidirectional"))
    )
    (net (code "89") (name "RTS1") (class "Default")
      (node (ref "R173") (pin "1") (pinfunction "1_1") (pintype "passive"))
      (node (ref "U101") (pin "55") (pinfunction "PF7_55") (pintype "bidirectional"))
    )
    (net (code "90") (name "RXD1") (class "Default")
      (node (ref "R224") (pin "1") (pinfunction "1_1") (pintype "passive"))
      (node (ref "U101") (pin "48") (pinfunction "PF2_48") (pintype "bidirectional"))
    )
    (net (code "91") (name "SCL1") (class "Default")
      (node (ref "R212") (pin "2") (pinfunction "2_2") (pintype "passive"))
      (node (ref "R401") (pin "1") (pinfunction "1_1") (pintype "passive"))
      (node (ref "U101") (pin "37") (pinfunction "PE1_37") (pintype "bidirectional"))
      (node (ref "U201") (pin "39") (pinfunction "SCL_39") (pintype "bidirectional"))
      (node (ref "U301") (pin "23") (pinfunction "SCL/SCLK_23") (pintype "input"))
      (node (ref "U401") (pin "8") (pinfunction "SCL_SCLK_8") (pintype "input"))
      (node (ref "U501") (pin "4") (pinfunction "SCL_4") (pintype "input"))
    )
    (net (code "92") (name "SCL2") (class "Default")
      (node (ref "U101") (pin "17") (pinfunction "PC1_17") (pintype "bidirectional"))
      (node (ref "X121") (pin "2") (pinfunction "2_2") (pintype "passive"))
    )
    (net (code "93") (name "SDA1") (class "Default")
      (node (ref "R211") (pin "2") (pinfunction "2_2") (pintype "passive"))
      (node (ref "R402") (pin "1") (pinfunction "1_1") (pintype "passive"))
      (node (ref "U101") (pin "36") (pinfunction "PE0_36") (pintype "bidirectional"))
      (node (ref "U201") (pin "38") (pinfunction "SDA_38") (pintype "bidirectional"))
      (node (ref "U301") (pin "24") (pinfunction "SDA/SDI_24") (pintype "bidirectional"))
      (node (ref "U401") (pin "7") (pinfunction "SDI_SDA_7") (pintype "bidirectional"))
      (node (ref "U501") (pin "1") (pinfunction "SDA_1") (pintype "bidirectional"))
    )
    (net (code "94") (name "SDA2") (class "Default")
      (node (ref "U101") (pin "16") (pinfunction "PC0_16") (pintype "bidirectional"))
      (node (ref "X121") (pin "4") (pinfunction "4_4") (pintype "passive"))
    )
    (net (code "95") (name "SIM_CLK") (class "Default")
      (node (ref "U201") (pin "31") (pinfunction "SIM_CLK_31") (pintype "output"))
      (node (ref "X801") (pin "S3") (pinfunction "S3_S3") (pintype "input"))
    )
    (net (code "96") (name "SIM_IO") (class "Default")
      (node (ref "U201") (pin "30") (pinfunction "SIM_DATA_30") (pintype "bidirectional"))
      (node (ref "X801") (pin "S7") (pinfunction "S7_S7") (pintype "bidirectional"))
    )
    (net (code "97") (name "SIM_RST") (class "Default")
      (node (ref "U201") (pin "32") (pinfunction "SIM_RST_32") (pintype "output"))
      (node (ref "X801") (pin "S2") (pinfunction "S2_S2") (pintype "bidirectional"))
    )
    (net (code "98") (name "SIM_VBUS") (class "Default")
      (node (ref "JP201") (pin "2") (pinfunction "2_2") (pintype "passive"))
      (node (ref "U201") (pin "25") (pinfunction "VBUS_25") (pintype "power_in"))
    )
    (net (code "99") (name "SIM_VCC") (class "Default")
      (node (ref "U201") (pin "29") (pinfunction "SIM_VDD_29") (pintype "power_in"))
      (node (ref "X801") (pin "S1") (pinfunction "S1_S1") (pintype "power_in"))
    )
    (net (code "100") (name "SIM_VPP") (class "Default")
      (node (ref "U201") (pin "33") (pinfunction "SIM_PRE_33") (pintype "input"))
      (node (ref "X801") (pin "S6") (pinfunction "S6_S6") (pintype "power_in"))
    )
    (net (code "101") (name "SW") (class "Default")
      (node (ref "D1111") (pin "C") (pinfunction "C_C") (pintype "passive"))
      (node (ref "L1111") (pin "2") (pinfunction "2_2") (pintype "passive"))
      (node (ref "U1111") (pin "1") (pinfunction "SW_1") (pintype "output"))
    )
    (net (code "102") (name "T4") (class "Default")
      (node (ref "X801") (pin "T4") (pinfunction "T4_T4") (pintype "power_in"))
    )
    (net (code "103") (name "TCK") (class "Default")
      (node (ref "U101") (pin "12") (pinfunction "PB6_12") (pintype "bidirectional"))
      (node (ref "X111") (pin "1") (pinfunction "1_1") (pintype "passive"))
    )
    (net (code "104") (name "TCXO_20MHZ") (class "Default")
      (node (ref "R1013") (pin "2") (pinfunction "2_2") (pintype "passive"))
      (node (ref "U101") (pin "59") (pinfunction "PR1_59") (pintype "bidirectional"))
    )
    (net (code "105") (name "TDI") (class "Default")
      (node (ref "U101") (pin "11") (pinfunction "PB5_11") (pintype "bidirectional"))
      (node (ref "X111") (pin "9") (pinfunction "9_9") (pintype "passive"))
    )
    (net (code "106") (name "TDO") (class "Default")
      (node (ref "U101") (pin "13") (pinfunction "PB7_13") (pintype "bidirectional"))
      (node (ref "X111") (pin "3") (pinfunction "3_3") (pintype "passive"))
    )
    (net (code "107") (name "TMS") (class "Default")
      (node (ref "U101") (pin "10") (pinfunction "PB4_10") (pintype "bidirectional"))
      (node (ref "X111") (pin "5") (pinfunction "5_5") (pintype "passive"))
    )
    (net (code "108") (name "TRSH") (class "Default")
      (node (ref "C1011") (pin "1") (pinfunction "1_1") (pintype "passive"))
      (node (ref "R1011") (pin "2") (pinfunction "2_2") (pintype "passive"))
      (node (ref "R1012") (pin "1") (pinfunction "1_1") (pintype "passive"))
      (node (ref "U1011") (pin "4") (pinfunction "-IN_4") (pintype "input"))
    )
    (net (code "109") (name "TXD1") (class "Default")
      (node (ref "R172") (pin "1") (pinfunction "1_1") (pintype "passive"))
      (node (ref "U101") (pin "49") (pinfunction "PF3_49") (pintype "bidirectional"))
    )
    (net (code "110") (name "USB_D_N") (class "Default")
      (node (ref "D722") (pin "C") (pinfunction "C_C") (pintype "passive"))
      (node (ref "R722") (pin "2") (pinfunction "2_2") (pintype "passive"))
      (node (ref "U101") (pin "32") (pinfunction "PD6_32") (pintype "bidirectional"))
    )
    (net (code "111") (name "USB_D_P") (class "Default")
      (node (ref "D721") (pin "C") (pinfunction "C_C") (pintype "passive"))
      (node (ref "R723") (pin "2") (pinfunction "2_2") (pintype "passive"))
      (node (ref "U101") (pin "33") (pinfunction "PD7_33") (pintype "bidirectional"))
    )
    (net (code "112") (name "USB_ID") (class "Default")
      (node (ref "R725") (pin "2") (pinfunction "2_2") (pintype "passive"))
      (node (ref "U101") (pin "7") (pinfunction "PB1_7") (pintype "bidirectional"))
    )
    (net (code "113") (name "USB_RESET") (class "Default")
      (node (ref "R151") (pin "2") (pinfunction "2_2") (pintype "passive"))
      (node (ref "R721") (pin "2") (pinfunction "2_2") (pintype "passive"))
    )
    (net (code "114") (name "USB_RESET_DRV") (class "Default")
      (node (ref "R151") (pin "1") (pinfunction "1_1") (pintype "passive"))
      (node (ref "U101") (pin "31") (pinfunction "PD5_31") (pintype "bidirectional"))
    )
    (net (code "115") (name "VBAT") (class "Default")
      (node (ref "C201") (pin "1") (pinfunction "1_1") (pintype "passive"))
      (node (ref "C901") (pin "1") (pinfunction "1_1") (pintype "passive"))
      (node (ref "D1122") (pin "A") (pinfunction "A_A") (pintype "passive"))
      (node (ref "D201") (pin "C") (pinfunction "C_C") (pintype "passive"))
      (node (ref "R1132") (pin "1") (pinfunction "1_1") (pintype "passive"))
      (node (ref "RPOLY901") (pin "2") (pinfunction "2_2") (pintype "passive"))
      (node (ref "U201") (pin "4") (pinfunction "VBAT_4") (pintype "power_in"))
      (node (ref "U201") (pin "5") (pinfunction "VBAT_5") (pintype "power_in"))
      (node (ref "U201") (pin "6") (pinfunction "VBAT_6") (pintype "power_in"))
    )
    (net (code "116") (name "VREF") (class "Default")
      (node (ref "R111") (pin "1") (pinfunction "1_1") (pintype "passive"))
      (node (ref "X111") (pin "4") (pinfunction "4_4") (pintype "passive"))
    )
    (net (code "117") (name "XO_AMP") (class "Default")
      (node (ref "R1013") (pin "1") (pinfunction "1_1") (pintype "passive"))
      (node (ref "U1011") (pin "1") (pinfunction "OUT_1") (pintype "output"))
    )
    (net (code "118") (name "XO_DRV") (class "Default")
      (node (ref "U1001") (pin "3") (pinfunction "OUT_3") (pintype "output"))
      (node (ref "U1011") (pin "3") (pinfunction "+IN_3") (pintype "input"))
    )
    (net (code "119") (name "XO_LP") (class "Default")
      (node (ref "C1001") (pin "1") (pinfunction "1_1") (pintype "passive"))
      (node (ref "R1001") (pin "2") (pinfunction "2_2") (pintype "passive"))
      (node (ref "R1002") (pin "1") (pinfunction "1_1") (pintype "passive"))
      (node (ref "U1021") (pin "3") (pinfunction "+IN_3") (pintype "input"))
    )
    (net (code "120") (name "XO_VC") (class "Default")
      (node (ref "R1002") (pin "2") (pinfunction "2_2") (pintype "passive"))
      (node (ref "U1001") (pin "1") (pinfunction "VC_1") (pintype "input"))
    )
    (net (code "121") (name "XO_VC_PWM") (class "Default")
      (node (ref "R1001") (pin "1") (pinfunction "1_1") (pintype "passive"))
      (node (ref "U101") (pin "18") (pinfunction "PC2_18") (pintype "bidirectional"))
    )
    (net (code "122") (name "unconnected-(U201-ADC1-Pad23)") (class "Default")
      (node (ref "U201") (pin "23") (pinfunction "ADC1_23") (pintype "input"))
    )
    (net (code "123") (name "unconnected-(U201-ADC2-Pad24)") (class "Default")
      (node (ref "U201") (pin "24") (pinfunction "ADC2_24") (pintype "input"))
    )
    (net (code "124") (name "unconnected-(U201-COL0-Pad62)") (class "Default")
      (node (ref "U201") (pin "62") (pinfunction "COL0_62") (pintype "input"))
    )
    (net (code "125") (name "unconnected-(U201-COL1-Pad61)") (class "Default")
      (node (ref "U201") (pin "61") (pinfunction "COL1_61") (pintype "input"))
    )
    (net (code "126") (name "unconnected-(U201-COL2-Pad60)") (class "Default")
      (node (ref "U201") (pin "60") (pinfunction "COL2_60") (pintype "input"))
    )
    (net (code "127") (name "unconnected-(U201-COL3-Pad59)") (class "Default")
      (node (ref "U201") (pin "59") (pinfunction "COL3_59") (pintype "input"))
    )
    (net (code "128") (name "unconnected-(U201-GPIO5-Pad43)") (class "Default")
      (node (ref "U201") (pin "43") (pinfunction "GPIO5_43") (pintype "bidirectional"))
    )
    (net (code "129") (name "unconnected-(U201-GPIO6-Pad44)") (class "Default")
      (node (ref "U201") (pin "44") (pinfunction "GPIO6_44") (pintype "bidirectional"))
    )
    (net (code "130") (name "unconnected-(U201-MIC1N-Pad20)") (class "Default")
      (node (ref "U201") (pin "20") (pinfunction "MIC1N_20") (pintype "input"))
    )
    (net (code "131") (name "unconnected-(U201-MIC1P-Pad19)") (class "Default")
      (node (ref "U201") (pin "19") (pinfunction "MIC1P_19") (pintype "input"))
    )
    (net (code "132") (name "unconnected-(U201-PWM1-Pad42)") (class "Default")
      (node (ref "U201") (pin "42") (pinfunction "PWM1_42") (pintype "output"))
    )
    (net (code "133") (name "unconnected-(U201-PWM2-Pad41)") (class "Default")
      (node (ref "U201") (pin "41") (pinfunction "PWM2_41") (pintype "output"))
    )
    (net (code "134") (name "unconnected-(U201-ROW0-Pad58)") (class "Default")
      (node (ref "U201") (pin "58") (pinfunction "ROW0_58") (pintype "output"))
    )
    (net (code "135") (name "unconnected-(U201-ROW1-Pad57)") (class "Default")
      (node (ref "U201") (pin "57") (pinfunction "ROW1_57") (pintype "output"))
    )
    (net (code "136") (name "unconnected-(U201-ROW2-Pad56)") (class "Default")
      (node (ref "U201") (pin "56") (pinfunction "ROW2_56") (pintype "output"))
    )
    (net (code "137") (name "unconnected-(U201-ROW3-Pad55)") (class "Default")
      (node (ref "U201") (pin "55") (pinfunction "ROW3_55") (pintype "output"))
    )
    (net (code "138") (name "unconnected-(U201-SPK1N-Pad22)") (class "Default")
      (node (ref "U201") (pin "22") (pinfunction "SPK1N_22") (pintype "output"))
    )
    (net (code "139") (name "unconnected-(U201-SPK1P-Pad21)") (class "Default")
      (node (ref "U201") (pin "21") (pinfunction "SPK1P_21") (pintype "output"))
    )
    (net (code "140") (name "unconnected-(U201-USB_DM-Pad27)") (class "Default")
      (node (ref "U201") (pin "27") (pinfunction "USB_DM_27") (pintype "bidirectional"))
    )
    (net (code "141") (name "unconnected-(U201-USB_DP-Pad26)") (class "Default")
      (node (ref "U201") (pin "26") (pinfunction "USB_DP_26") (pintype "bidirectional"))
    )
    (net (code "142") (name "unconnected-(U301-AUX_CL-Pad7)") (class "Default")
      (node (ref "U301") (pin "7") (pinfunction "AUX_CL_7") (pintype "output"))
    )
    (net (code "143") (name "unconnected-(U301-AUX_DA-Pad21)") (class "Default")
      (node (ref "U301") (pin "21") (pinfunction "AUX_DA_21") (pintype "bidirectional"))
    )
    (net (code "144") (name "unconnected-(U401-NC-Pad5)") (class "Default")
      (node (ref "U401") (pin "5") (pinfunction "NC_5") (pintype "no_connect"))
    )
    (net (code "145") (name "unconnected-(U401-SDO-Pad6)") (class "Default")
      (node (ref "U401") (pin "6") (pinfunction "SDO_6") (pintype "output"))
    )
    (net (code "146") (name "unconnected-(U501-ALERT-Pad3)") (class "Default")
      (node (ref "U501") (pin "3") (pinfunction "ALERT_3") (pintype "output"))
    )
    (net (code "147") (name "unconnected-(U501-~{RESET}-Pad6)") (class "Default")
      (node (ref "U501") (pin "6") (pinfunction "~{RESET}_6") (pintype "passive"))
    )
    (net (code "148") (name "unconnected-(U601-FILT-Pad6)") (class "Default")
      (node (ref "U601") (pin "6") (pinfunction "FILT_6") (pintype "passive"))
    )
    (net (code "149") (name "unconnected-(U601-SYSCLK-Pad9)") (class "Default")
      (node (ref "U601") (pin "9") (pinfunction "SYSCLK_9") (pintype "bidirectional"))
    )
    (net (code "150") (name "unconnected-(U601-TCXO_EN-Pad15)") (class "Default")
      (node (ref "U601") (pin "15") (pinfunction "TCXO_EN_15") (pintype "bidirectional"))
    )
    (net (code "151") (name "unconnected-(U1121-REF-Pad1)") (class "Default")
      (node (ref "U1121") (pin "1") (pinfunction "REF_1") (pintype "no_connect"))
    )
    (net (code "152") (name "unconnected-(X111-Pad8)") (class "Default")
      (node (ref "X111") (pin "8") (pinfunction "8_8") (pintype "passive"))
    )
    (net (code "153") (name "unconnected-(X131-Pad3)") (class "Default")
      (node (ref "X131") (pin "3") (pinfunction "3_3") (pintype "passive"))
    )
    (net (code "154") (name "unconnected-(X131-Pad4)") (class "Default")
      (node (ref "X131") (pin "4") (pinfunction "4_4") (pintype "passive"))
    )
    (net (code "155") (name "unconnected-(X801-PadS4)") (class "Default")
      (node (ref "X801") (pin "S4") (pinfunction "S4_S4") (pintype "passive"))
    )
    (net (code "156") (name "unconnected-(X801-PadS8)") (class "Default")
      (node (ref "X801") (pin "S8") (pinfunction "S8_S8") (pintype "passive"))
    )
    (net (code "157") (name "unconnected-(X801-PadSW)") (class "Default")
      (node (ref "X801") (pin "SW") (pinfunction "SW_SW") (pintype "passive"))
    )
    (net (code "158") (name "unconnected-(X801-PadT1)") (class "Default")
      (node (ref "X801") (pin "T1") (pinfunction "T1_T1") (pintype "bidirectional"))
    )
    (net (code "159") (name "unconnected-(X801-PadT2)") (class "Default")
      (node (ref "X801") (pin "T2") (pinfunction "T2_T2") (pintype "bidirectional"))
    )
    (net (code "160") (name "unconnected-(X801-PadT3)") (class "Default")
      (node (ref "X801") (pin "T3") (pinfunction "T3_T3") (pintype "bidirectional"))
    )
    (net (code "161") (name "unconnected-(X801-PadT5)") (class "Default")
      (node (ref "X801") (pin "T5") (pinfunction "T5_T5") (pintype "input"))
    )
    (net (code "162") (name "unconnected-(X801-PadT7)") (class "Default")
      (node (ref "X801") (pin "T7") (pinfunction "T7_T7") (pintype "bidirectional"))
    )
    (net (code "163") (name "unconnected-(X801-PadT8)") (class "Default")
      (node (ref "X801") (pin "T8") (pinfunction "T8_T8") (pintype "bidirectional"))
    )
    (net (code "164") (name "unconnected-(X901-Pad2)") (class "Default")
      (node (ref "X901") (pin "2") (pinfunction "2_2") (pintype "passive"))
    )
  )
)
